# InkTimevf.net
KiCad netlist of a schematic drawn in EAGLE
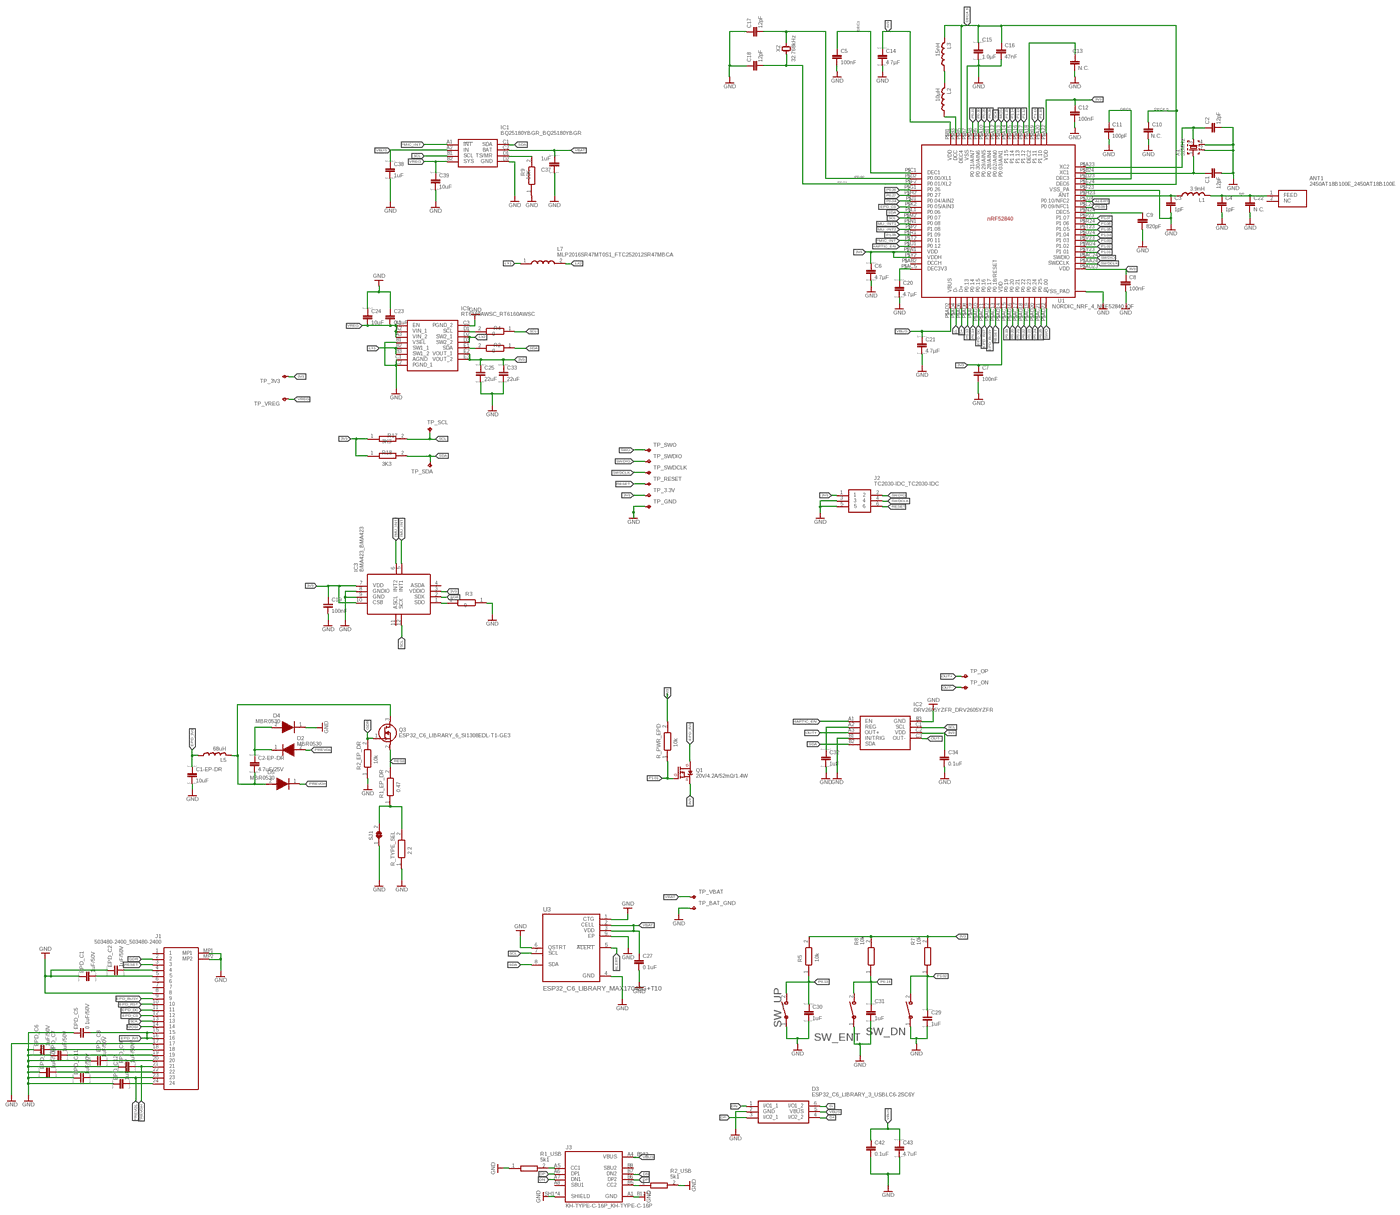
[diagram p0: schematic, sheet 1, overview]
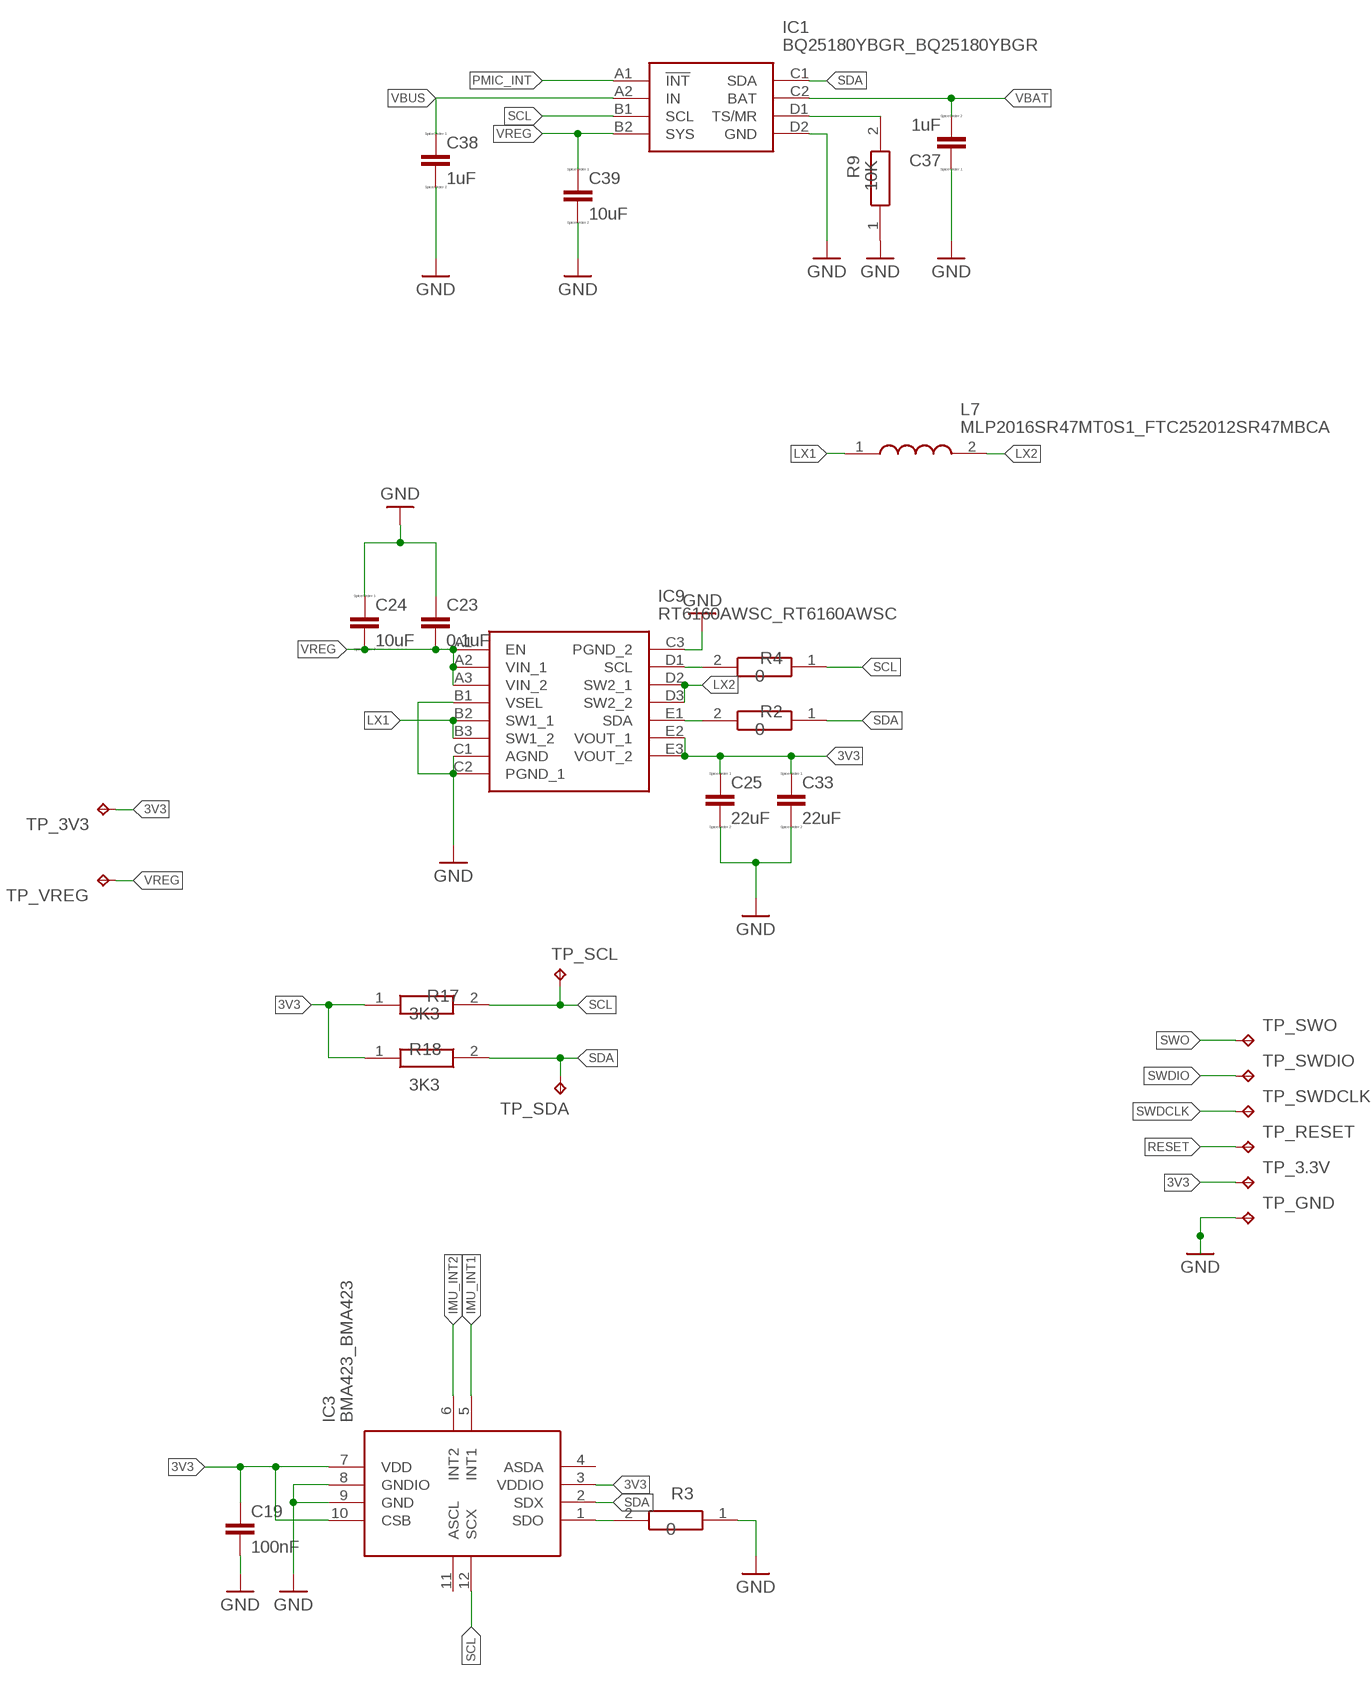
[diagram p1: schematic, sheet 1, part 1 of 4]
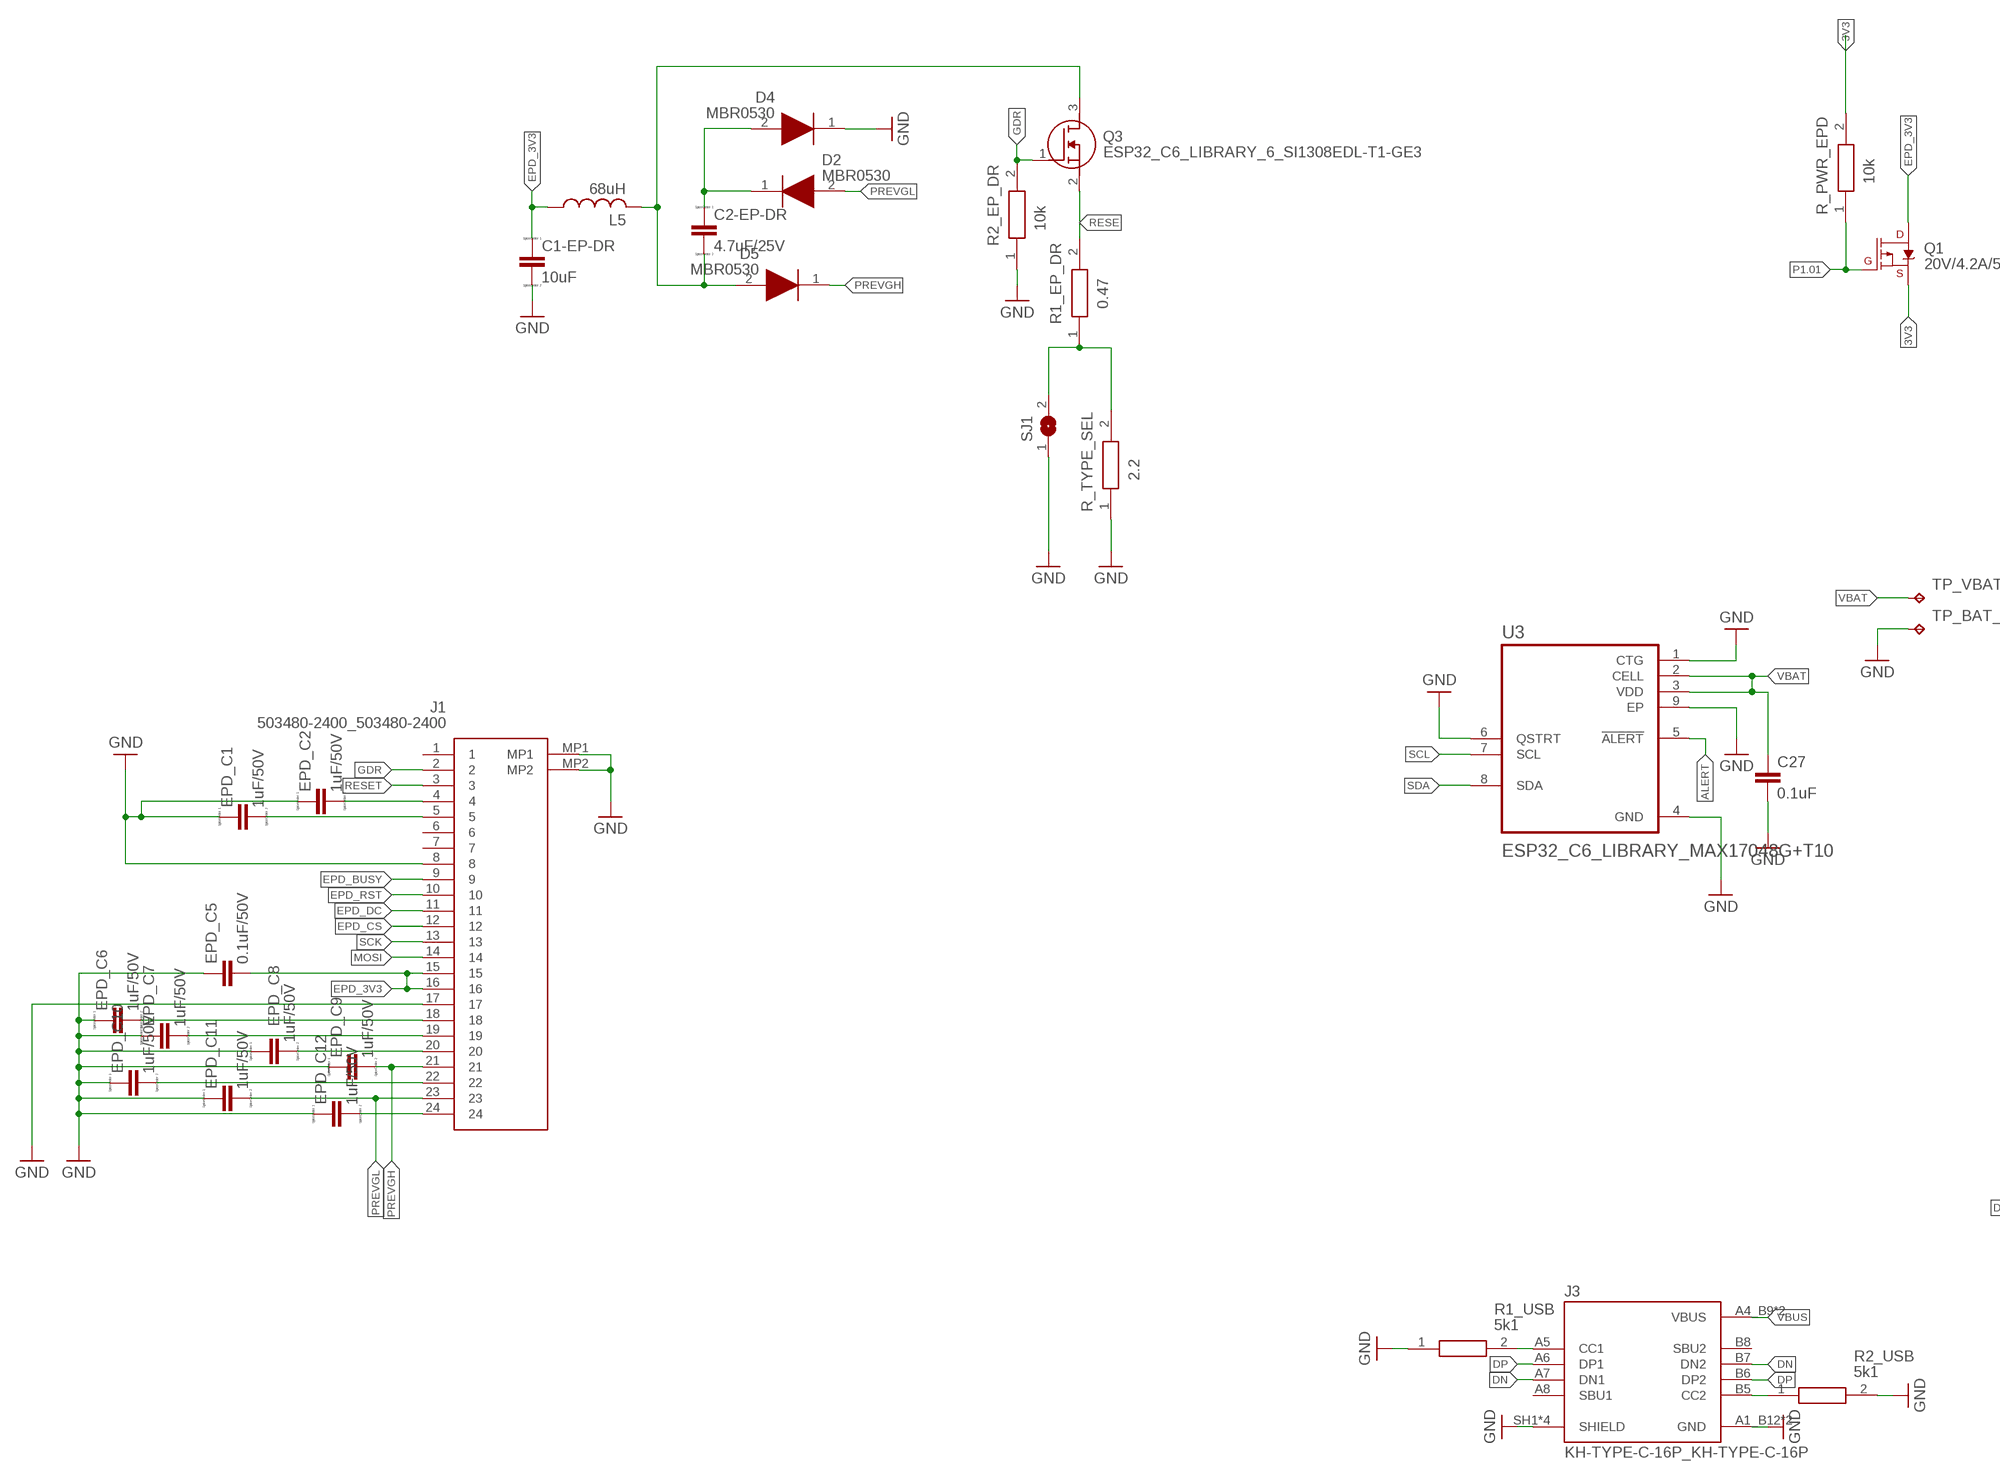
[diagram p2: schematic, sheet 1, part 2 of 4]
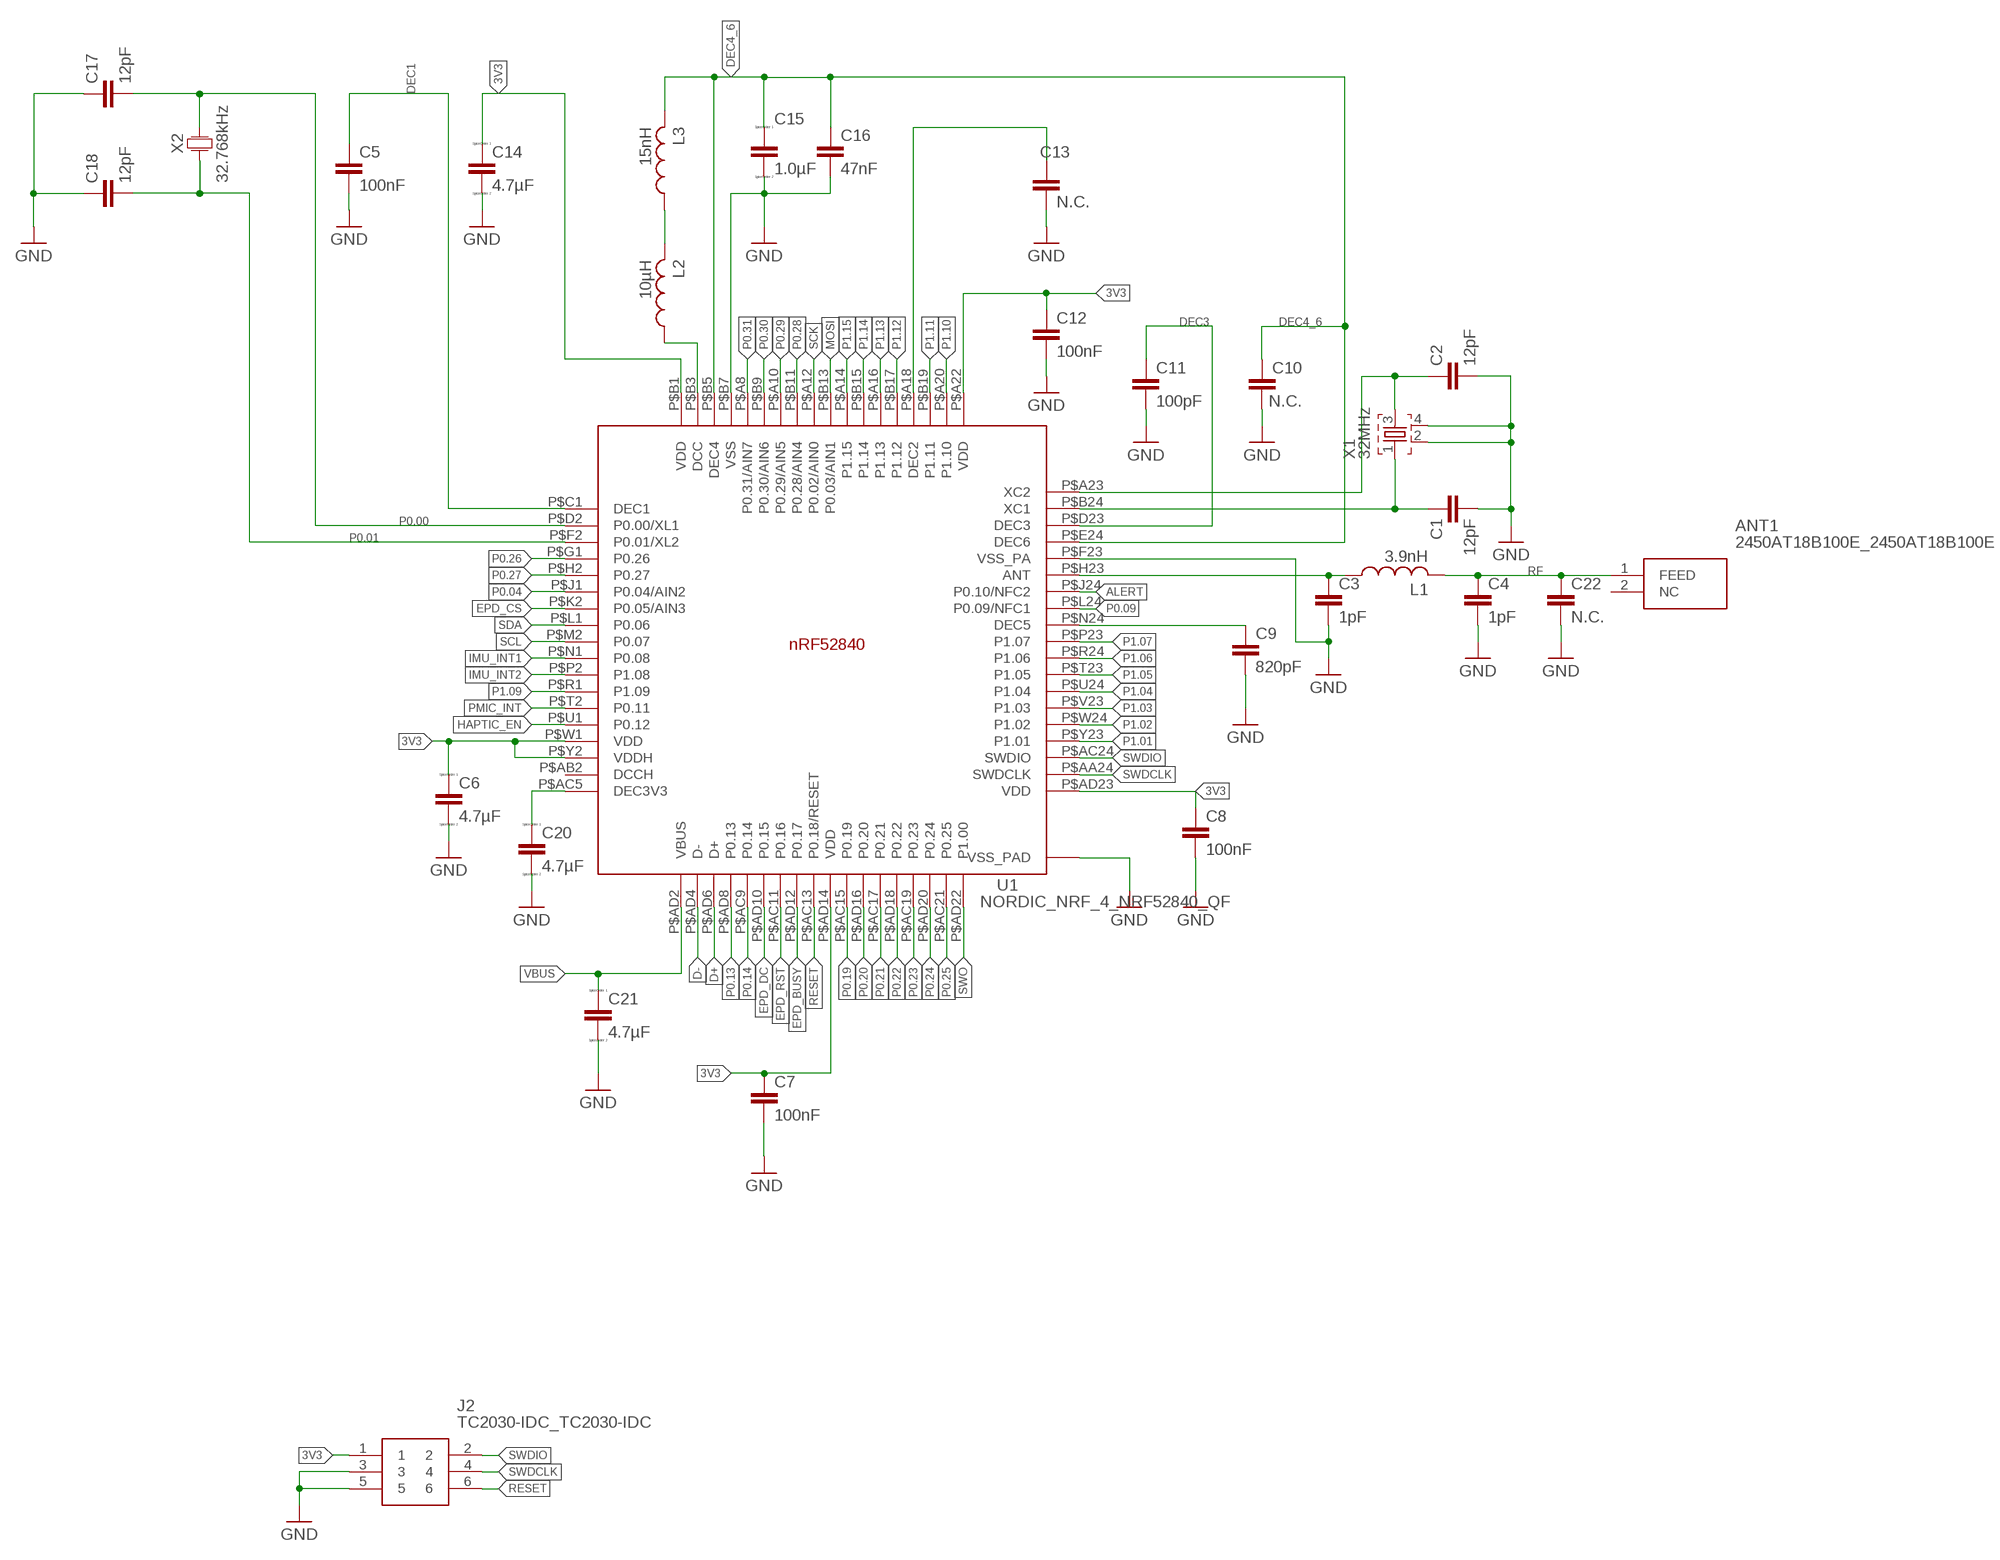
[diagram p3: schematic, sheet 1, part 3 of 4]
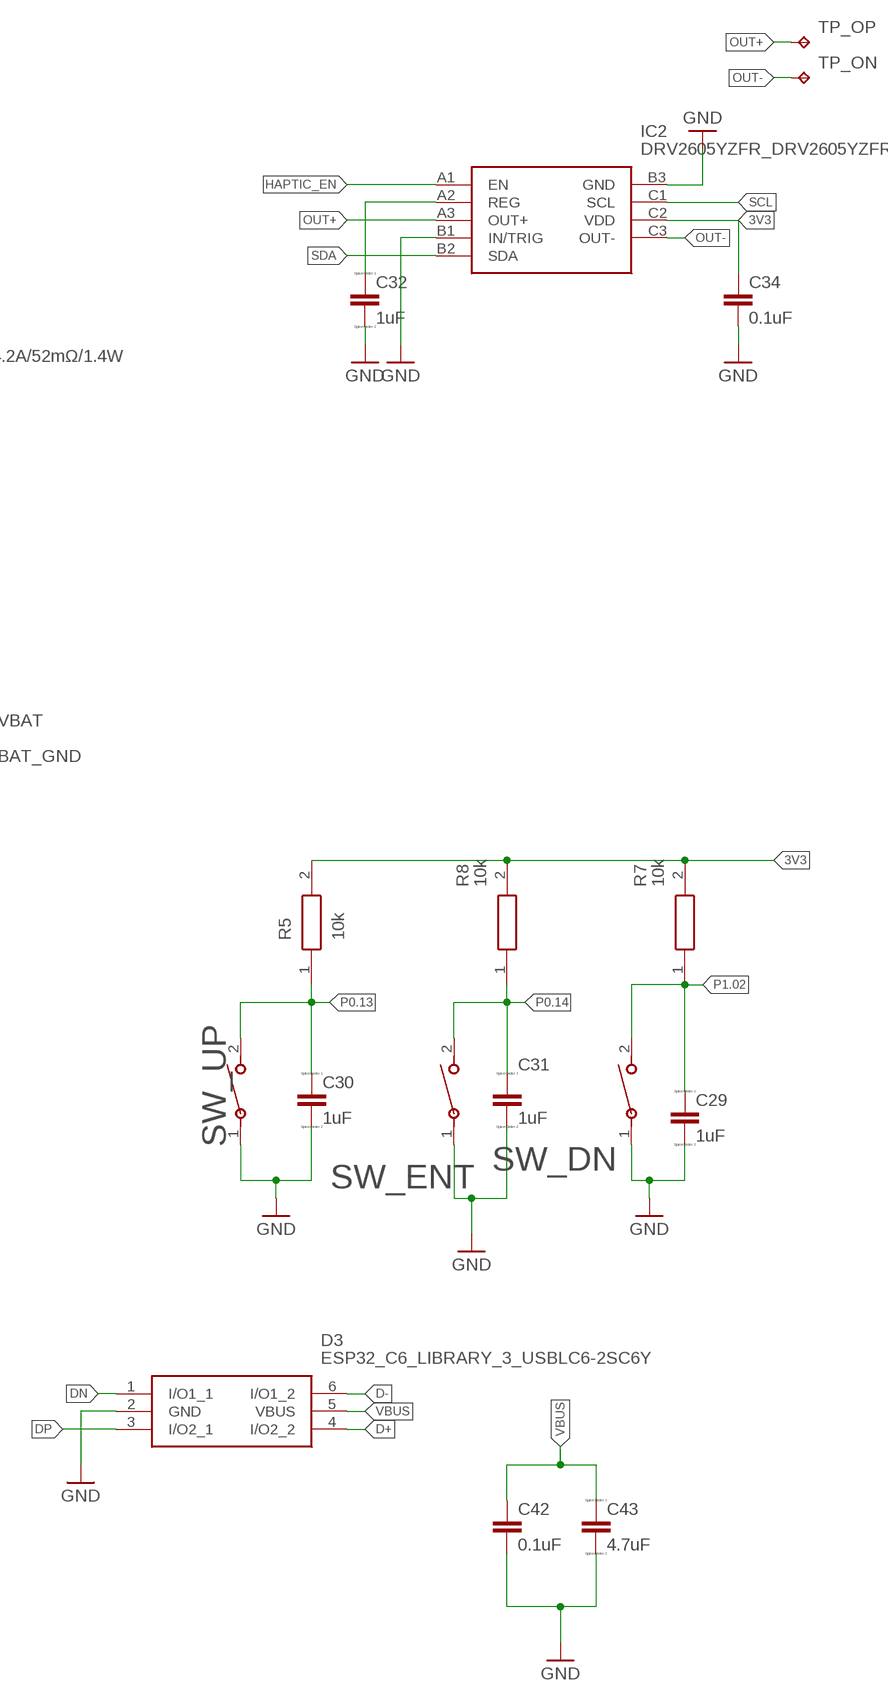
[diagram p4: schematic, sheet 1, part 4 of 4]

(export (version "E")
  (design (tool "Eeschema 10.0.6"))
  (components
    (comp (ref "ANT1")
      (value "2450AT18B100E_2450AT18B100E")
      (footprint "eagle-import:2450AT18B100E_ANTC3216X140N")
      (fields
        (field (name "ARROW_PART_NUMBER") "2450AT18B100E")
        (field (name "MOUSER_PART_NUMBER") "609-2450AT18B100E")
      )
      (libsource (lib "eagle-import") (part "2450AT18B100E_2450AT18B100E"))
    )
    (comp (ref "C1")
      (value "12pF")
      (footprint "eagle-import:NORDIC_NRF_3_RESC0201_L")
      (libsource (lib "eagle-import") (part "NORDIC_NRF_3_CAPACITOR_0201_L"))
    )
    (comp (ref "C1-EP-DR")
      (value "10uF")
      (footprint "eagle-import:ESP32_C6_LIBRARY_1_ESP32_WROVER_EAGLE-LTSPICE_C0402")
      (libsource (lib "eagle-import") (part "ESP32_C6_LIBRARY_1_ESP32_WROVER_EAGLE-LTSPICE_CC0402"))
    )
    (comp (ref "C2")
      (value "12pF")
      (footprint "eagle-import:NORDIC_NRF_3_RESC0201_L")
      (libsource (lib "eagle-import") (part "NORDIC_NRF_3_CAPACITOR_0201_L"))
    )
    (comp (ref "C2-EP-DR")
      (value "4.7uF/25V")
      (footprint "eagle-import:ESP32_C6_LIBRARY_1_ESP32_WROVER_EAGLE-LTSPICE_C0402")
      (libsource (lib "eagle-import") (part "ESP32_C6_LIBRARY_1_ESP32_WROVER_EAGLE-LTSPICE_CC0402"))
    )
    (comp (ref "C3")
      (value "1pF")
      (footprint "eagle-import:NORDIC_NRF_3_RESC0201_L")
      (libsource (lib "eagle-import") (part "NORDIC_NRF_3_CAPACITOR_0201_L"))
    )
    (comp (ref "C4")
      (value "1pF")
      (footprint "eagle-import:NORDIC_NRF_3_RESC0201_L")
      (libsource (lib "eagle-import") (part "NORDIC_NRF_3_CAPACITOR_0201_L"))
    )
    (comp (ref "C5")
      (value "100nF")
      (footprint "eagle-import:NORDIC_NRF_3_RESC0201_L")
      (libsource (lib "eagle-import") (part "NORDIC_NRF_3_CAPACITOR_0201_L"))
    )
    (comp (ref "C6")
      (value "4.7µF")
      (footprint "eagle-import:ESP32_C6_LIBRARY_1_ESP32_WROVER_EAGLE-LTSPICE_C0402")
      (libsource (lib "eagle-import") (part "ESP32_C6_LIBRARY_1_ESP32_WROVER_EAGLE-LTSPICE_CC0402"))
    )
    (comp (ref "C7")
      (value "100nF")
      (footprint "eagle-import:NORDIC_NRF_3_RESC0201_L")
      (libsource (lib "eagle-import") (part "NORDIC_NRF_3_CAPACITOR_0201_L"))
    )
    (comp (ref "C8")
      (value "100nF")
      (footprint "eagle-import:NORDIC_NRF_3_RESC0201_L")
      (libsource (lib "eagle-import") (part "NORDIC_NRF_3_CAPACITOR_0201_L"))
    )
    (comp (ref "C9")
      (value "820pF")
      (footprint "eagle-import:NORDIC_NRF_3_RESC0201_L")
      (libsource (lib "eagle-import") (part "NORDIC_NRF_3_CAPACITOR_0201_L"))
    )
    (comp (ref "C10")
      (value "N.C.")
      (footprint "eagle-import:NORDIC_NRF_3_RESC0201_L")
      (libsource (lib "eagle-import") (part "NORDIC_NRF_3_CAPACITOR_0201_L"))
    )
    (comp (ref "C11")
      (value "100pF")
      (footprint "eagle-import:NORDIC_NRF_3_RESC0201_L")
      (libsource (lib "eagle-import") (part "NORDIC_NRF_3_CAPACITOR_0201_L"))
    )
    (comp (ref "C12")
      (value "100nF")
      (footprint "eagle-import:NORDIC_NRF_3_RESC0201_L")
      (libsource (lib "eagle-import") (part "NORDIC_NRF_3_CAPACITOR_0201_L"))
    )
    (comp (ref "C13")
      (value "N.C.")
      (footprint "eagle-import:NORDIC_NRF_3_RESC0201_L")
      (libsource (lib "eagle-import") (part "NORDIC_NRF_3_CAPACITOR_0201_L"))
    )
    (comp (ref "C14")
      (value "4.7µF")
      (footprint "eagle-import:ESP32_C6_LIBRARY_1_ESP32_WROVER_EAGLE-LTSPICE_C0402")
      (libsource (lib "eagle-import") (part "ESP32_C6_LIBRARY_1_ESP32_WROVER_EAGLE-LTSPICE_CC0402"))
    )
    (comp (ref "C15")
      (value "1.0µF")
      (footprint "eagle-import:ESP32_C6_LIBRARY_1_ESP32_WROVER_EAGLE-LTSPICE_C0402")
      (libsource (lib "eagle-import") (part "ESP32_C6_LIBRARY_1_ESP32_WROVER_EAGLE-LTSPICE_CC0402"))
    )
    (comp (ref "C16")
      (value "47nF")
      (footprint "eagle-import:NORDIC_NRF_3_RESC0201_L")
      (libsource (lib "eagle-import") (part "NORDIC_NRF_3_CAPACITOR_0201_L"))
    )
    (comp (ref "C17")
      (value "12pF")
      (footprint "eagle-import:NORDIC_NRF_3_RESC0201_L")
      (libsource (lib "eagle-import") (part "NORDIC_NRF_3_CAPACITOR_0201_L"))
    )
    (comp (ref "C18")
      (value "12pF")
      (footprint "eagle-import:NORDIC_NRF_3_RESC0201_L")
      (libsource (lib "eagle-import") (part "NORDIC_NRF_3_CAPACITOR_0201_L"))
    )
    (comp (ref "C19")
      (value "100nF")
      (footprint "eagle-import:NORDIC_NRF_3_RESC0201_L")
      (libsource (lib "eagle-import") (part "NORDIC_NRF_3_CAPACITOR_0201_L"))
    )
    (comp (ref "C20")
      (value "4.7µF")
      (footprint "eagle-import:ESP32_C6_LIBRARY_1_ESP32_WROVER_EAGLE-LTSPICE_C0402")
      (libsource (lib "eagle-import") (part "ESP32_C6_LIBRARY_1_ESP32_WROVER_EAGLE-LTSPICE_CC0402"))
    )
    (comp (ref "C21")
      (value "4.7µF")
      (footprint "eagle-import:ESP32_C6_LIBRARY_1_ESP32_WROVER_EAGLE-LTSPICE_C0402")
      (libsource (lib "eagle-import") (part "ESP32_C6_LIBRARY_1_ESP32_WROVER_EAGLE-LTSPICE_CC0402"))
    )
    (comp (ref "C22")
      (value "N.C.")
      (footprint "eagle-import:NORDIC_NRF_3_RESC0201_L")
      (libsource (lib "eagle-import") (part "NORDIC_NRF_3_CAPACITOR_0201_L"))
    )
    (comp (ref "C23")
      (value "0.1uF")
      (footprint "eagle-import:NORDIC_NRF_3_RESC0201_L")
      (libsource (lib "eagle-import") (part "NORDIC_NRF_3_CAPACITOR_0201_L"))
    )
    (comp (ref "C24")
      (value "10uF")
      (footprint "eagle-import:ESP32_C6_LIBRARY_1_ESP32_WROVER_EAGLE-LTSPICE_C0402")
      (libsource (lib "eagle-import") (part "ESP32_C6_LIBRARY_1_ESP32_WROVER_EAGLE-LTSPICE_CC0402"))
    )
    (comp (ref "C25")
      (value "22uF")
      (footprint "eagle-import:ESP32_C6_LIBRARY_1_ESP32_WROVER_EAGLE-LTSPICE_C0402")
      (libsource (lib "eagle-import") (part "ESP32_C6_LIBRARY_1_ESP32_WROVER_EAGLE-LTSPICE_CC0402"))
    )
    (comp (ref "C27")
      (value "0.1uF")
      (footprint "eagle-import:NORDIC_NRF_3_RESC0201_L")
      (libsource (lib "eagle-import") (part "NORDIC_NRF_3_CAPACITOR_0201_L"))
    )
    (comp (ref "C29")
      (value "1uF")
      (footprint "eagle-import:ESP32_C6_LIBRARY_1_ESP32_WROVER_EAGLE-LTSPICE_C0402")
      (libsource (lib "eagle-import") (part "ESP32_C6_LIBRARY_1_ESP32_WROVER_EAGLE-LTSPICE_CC0402"))
    )
    (comp (ref "C30")
      (value "1uF")
      (footprint "eagle-import:ESP32_C6_LIBRARY_1_ESP32_WROVER_EAGLE-LTSPICE_C0402")
      (libsource (lib "eagle-import") (part "ESP32_C6_LIBRARY_1_ESP32_WROVER_EAGLE-LTSPICE_CC0402"))
    )
    (comp (ref "C31")
      (value "1uF")
      (footprint "eagle-import:ESP32_C6_LIBRARY_1_ESP32_WROVER_EAGLE-LTSPICE_C0402")
      (libsource (lib "eagle-import") (part "ESP32_C6_LIBRARY_1_ESP32_WROVER_EAGLE-LTSPICE_CC0402"))
    )
    (comp (ref "C32")
      (value "1uF")
      (footprint "eagle-import:ESP32_C6_LIBRARY_1_ESP32_WROVER_EAGLE-LTSPICE_C0402")
      (libsource (lib "eagle-import") (part "ESP32_C6_LIBRARY_1_ESP32_WROVER_EAGLE-LTSPICE_CC0402"))
    )
    (comp (ref "C33")
      (value "22uF")
      (footprint "eagle-import:ESP32_C6_LIBRARY_1_ESP32_WROVER_EAGLE-LTSPICE_C0402")
      (libsource (lib "eagle-import") (part "ESP32_C6_LIBRARY_1_ESP32_WROVER_EAGLE-LTSPICE_CC0402"))
    )
    (comp (ref "C34")
      (value "0.1uF")
      (footprint "eagle-import:NORDIC_NRF_3_RESC0201_L")
      (libsource (lib "eagle-import") (part "NORDIC_NRF_3_CAPACITOR_0201_L"))
    )
    (comp (ref "C37")
      (value "1uF")
      (footprint "eagle-import:ESP32_C6_LIBRARY_1_ESP32_WROVER_EAGLE-LTSPICE_C0402")
      (libsource (lib "eagle-import") (part "ESP32_C6_LIBRARY_1_ESP32_WROVER_EAGLE-LTSPICE_CC0402"))
    )
    (comp (ref "C38")
      (value "1uF")
      (footprint "eagle-import:ESP32_C6_LIBRARY_1_ESP32_WROVER_EAGLE-LTSPICE_C0402")
      (libsource (lib "eagle-import") (part "ESP32_C6_LIBRARY_1_ESP32_WROVER_EAGLE-LTSPICE_CC0402"))
    )
    (comp (ref "C39")
      (value "10uF")
      (footprint "eagle-import:ESP32_C6_LIBRARY_1_ESP32_WROVER_EAGLE-LTSPICE_C0402")
      (libsource (lib "eagle-import") (part "ESP32_C6_LIBRARY_1_ESP32_WROVER_EAGLE-LTSPICE_CC0402"))
    )
    (comp (ref "C42")
      (value "0.1uF")
      (footprint "eagle-import:NORDIC_NRF_3_RESC0201_L")
      (libsource (lib "eagle-import") (part "NORDIC_NRF_3_CAPACITOR_0201_L"))
    )
    (comp (ref "C43")
      (value "4.7uF")
      (footprint "eagle-import:ESP32_C6_LIBRARY_1_ESP32_WROVER_EAGLE-LTSPICE_C0402")
      (libsource (lib "eagle-import") (part "ESP32_C6_LIBRARY_1_ESP32_WROVER_EAGLE-LTSPICE_CC0402"))
    )
    (comp (ref "D2")
      (value "MBR0530")
      (footprint "eagle-import:ESP32_C6_LIBRARY_5_SOD3716X135N")
      (fields (field (name "MF") "ON Semiconductor"))
      (libsource (lib "eagle-import") (part "ESP32_C6_LIBRARY_5_MBR0530"))
    )
    (comp (ref "D3")
      (value "ESP32_C6_LIBRARY_3_USBLC6-2SC6Y")
      (footprint "eagle-import:ESP32_C6_LIBRARY_3_SOT95P280X145-6N")
      (fields (field (name "MF") "STMicroelectronics") (field (name "MP") "USBLC6-2SC6Y"))
      (libsource (lib "eagle-import") (part "ESP32_C6_LIBRARY_3_USBLC6-2SC6Y"))
    )
    (comp (ref "D4")
      (value "MBR0530")
      (footprint "eagle-import:ESP32_C6_LIBRARY_5_SOD3716X135N")
      (fields (field (name "MF") "ON Semiconductor"))
      (libsource (lib "eagle-import") (part "ESP32_C6_LIBRARY_5_MBR0530"))
    )
    (comp (ref "D5")
      (value "MBR0530")
      (footprint "eagle-import:ESP32_C6_LIBRARY_5_SOD3716X135N")
      (fields (field (name "MF") "ON Semiconductor"))
      (libsource (lib "eagle-import") (part "ESP32_C6_LIBRARY_5_MBR0530"))
    )
    (comp (ref "EPD_C1")
      (value "1uF/50V")
      (footprint "eagle-import:ESP32_C6_LIBRARY_1_ESP32_WROVER_EAGLE-LTSPICE_C0402")
      (libsource (lib "eagle-import") (part "ESP32_C6_LIBRARY_1_ESP32_WROVER_EAGLE-LTSPICE_CC0402"))
    )
    (comp (ref "EPD_C2")
      (value "1uF/50V")
      (footprint "eagle-import:ESP32_C6_LIBRARY_1_ESP32_WROVER_EAGLE-LTSPICE_C0402")
      (libsource (lib "eagle-import") (part "ESP32_C6_LIBRARY_1_ESP32_WROVER_EAGLE-LTSPICE_CC0402"))
    )
    (comp (ref "EPD_C5")
      (value "0.1uF/50V")
      (footprint "eagle-import:NORDIC_NRF_3_RESC0201_L")
      (libsource (lib "eagle-import") (part "NORDIC_NRF_3_CAPACITOR_0201_L"))
    )
    (comp (ref "EPD_C6")
      (value "1uF/50V")
      (footprint "eagle-import:ESP32_C6_LIBRARY_1_ESP32_WROVER_EAGLE-LTSPICE_C0402")
      (libsource (lib "eagle-import") (part "ESP32_C6_LIBRARY_1_ESP32_WROVER_EAGLE-LTSPICE_CC0402"))
    )
    (comp (ref "EPD_C7")
      (value "1uF/50V")
      (footprint "eagle-import:ESP32_C6_LIBRARY_1_ESP32_WROVER_EAGLE-LTSPICE_C0402")
      (libsource (lib "eagle-import") (part "ESP32_C6_LIBRARY_1_ESP32_WROVER_EAGLE-LTSPICE_CC0402"))
    )
    (comp (ref "EPD_C8")
      (value "1uF/50V")
      (footprint "eagle-import:ESP32_C6_LIBRARY_1_ESP32_WROVER_EAGLE-LTSPICE_C0402")
      (libsource (lib "eagle-import") (part "ESP32_C6_LIBRARY_1_ESP32_WROVER_EAGLE-LTSPICE_CC0402"))
    )
    (comp (ref "EPD_C9")
      (value "1uF/50V")
      (footprint "eagle-import:ESP32_C6_LIBRARY_1_ESP32_WROVER_EAGLE-LTSPICE_C0402")
      (libsource (lib "eagle-import") (part "ESP32_C6_LIBRARY_1_ESP32_WROVER_EAGLE-LTSPICE_CC0402"))
    )
    (comp (ref "EPD_C10")
      (value "1uF/50V")
      (footprint "eagle-import:ESP32_C6_LIBRARY_1_ESP32_WROVER_EAGLE-LTSPICE_C0402")
      (libsource (lib "eagle-import") (part "ESP32_C6_LIBRARY_1_ESP32_WROVER_EAGLE-LTSPICE_CC0402"))
    )
    (comp (ref "EPD_C11")
      (value "1uF/50V")
      (footprint "eagle-import:ESP32_C6_LIBRARY_1_ESP32_WROVER_EAGLE-LTSPICE_C0402")
      (libsource (lib "eagle-import") (part "ESP32_C6_LIBRARY_1_ESP32_WROVER_EAGLE-LTSPICE_CC0402"))
    )
    (comp (ref "EPD_C12")
      (value "1uF/50V")
      (footprint "eagle-import:ESP32_C6_LIBRARY_1_ESP32_WROVER_EAGLE-LTSPICE_C0402")
      (libsource (lib "eagle-import") (part "ESP32_C6_LIBRARY_1_ESP32_WROVER_EAGLE-LTSPICE_CC0402"))
    )
    (comp (ref "IC1")
      (value "BQ25180YBGR_BQ25180YBGR")
      (footprint "eagle-import:BQ25180YBGR_BGA8C40P2X4_100X155X50")
      (fields
        (field (name "ARROW_PART_NUMBER") "BQ25180YBGR")
        (field (name "MOUSER_PART_NUMBER") "595-BQ25180YBGR")
      )
      (libsource (lib "eagle-import") (part "BQ25180YBGR_BQ25180YBGR"))
    )
    (comp (ref "IC2")
      (value "DRV2605YZFR_DRV2605YZFR")
      (footprint "eagle-import:DRV2605YZFR_BGA9C50P3X3_144X144X62")
      (fields (field (name "ARROW_PART_NUMBER") "DRV2605YZFR"))
      (libsource (lib "eagle-import") (part "DRV2605YZFR_DRV2605YZFR"))
    )
    (comp (ref "IC3")
      (value "BMA423_BMA423")
      (footprint "eagle-import:BMA423_BMA423")
      (fields (field (name "ARROW_PART_NUMBER") "BMA423") (field (name "MOUSER_PART_NUMBER") "262-BMA423"))
      (libsource (lib "eagle-import") (part "BMA423_BMA423"))
    )
    (comp (ref "IC9")
      (value "RT6160AWSC_RT6160AWSC")
      (footprint "eagle-import:RT6160AWSC_BGA15C40P3X5_140X230X60")
      (fields
        (field (name "MANUFACTURER_PART_NUMBER") "RT6160AWSC")
        (field (name "MOUSER_PART_NUMBER") "835-RT6160AWSC")
      )
      (libsource (lib "eagle-import") (part "RT6160AWSC_RT6160AWSC"))
    )
    (comp (ref "J1")
      (value "503480-2400_503480-2400")
      (footprint "eagle-import:503480-2400_5034802400")
      (fields
        (field (name "MANUFACTURER_PART_NUMBER") "503480-2400")
        (field (name "MOUSER_PART_NUMBER") "538-503480-2400")
      )
      (libsource (lib "eagle-import") (part "503480-2400_503480-2400"))
    )
    (comp (ref "J2")
      (value "TC2030-IDC_TC2030-IDC")
      (footprint "eagle-import:TC2030-IDC_TC2030IDC")
      (fields (field (name "MANUFACTURER_PART_NUMBER") "TC2030-IDC"))
      (libsource (lib "eagle-import") (part "TC2030-IDC_TC2030-IDC"))
    )
    (comp (ref "J3")
      (value "KH-TYPE-C-16P_KH-TYPE-C-16P")
      (footprint "eagle-import:KH-TYPE-C-16P_KINGHELM_KH-TYPE-C-16P")
      (fields (field (name "MF") "kinghelm") (field (name "MP") "KH-TYPE-C-16P"))
      (libsource (lib "eagle-import") (part "KH-TYPE-C-16P_KH-TYPE-C-16P"))
    )
    (comp (ref "L1")
      (value "3.9nH")
      (footprint "eagle-import:NORDIC_NRF_2_RESC0402_L")
      (libsource (lib "eagle-import") (part "NORDIC_NRF_2_INDUCTOR_0402_L"))
    )
    (comp (ref "L2")
      (value "10µH")
      (footprint "eagle-import:NORDIC_NRF_2_RESC0402_L")
      (libsource (lib "eagle-import") (part "NORDIC_NRF_2_INDUCTOR_0402_L"))
    )
    (comp (ref "L3")
      (value "15nH")
      (footprint "eagle-import:NORDIC_NRF_2_RESC0402_L")
      (libsource (lib "eagle-import") (part "NORDIC_NRF_2_INDUCTOR_0402_L"))
    )
    (comp (ref "L5")
      (value "68uH")
      (footprint "eagle-import:NORDIC_NRF_2_RESC0402_L")
      (libsource (lib "eagle-import") (part "NORDIC_NRF_2_INDUCTOR_0402_L"))
    )
    (comp (ref "L7")
      (value "MLP2016SR47MT0S1_FTC252012SR47MBCA")
      (footprint "eagle-import:MLP2016SR47MT0S1_INDC2016X100N")
      (fields (field (name "MANUFACTURER_PART_NUMBER") "FTC252012SR47MBCA"))
      (libsource (lib "eagle-import") (part "MLP2016SR47MT0S1_FTC252012SR47MBCA"))
    )
    (comp (ref "Q1")
      (value "20V/4.2A/52mΩ/1.4W")
      (footprint "eagle-import:ESP32_C6_LIBRARY_4_ESP32_C6_LIBRARY_4_ESP32_C6_LIBRARY_4_ESP32_C6_LIBRARY_4_ESP32_WROVER_SPARKFUN-DISCRETESEMI_SOT23-3")
      (libsource (lib "eagle-import") (part "ESP32_C6_LIBRARY_4_ESP32_WROVER_SPARKFUN-DISCRETESEMI_MOSFET_PCH-DMG2305UX-7"))
    )
    (comp (ref "Q3")
      (value "ESP32_C6_LIBRARY_6_SI1308EDL-T1-GE3")
      (footprint "eagle-import:ESP32_C6_LIBRARY_6_SOT65P210X110-3N")
      (fields (field (name "MF") "Vishay Siliconix") (field (name "MP") "SI1308EDL-T1-GE3"))
      (libsource (lib "eagle-import") (part "ESP32_C6_LIBRARY_6_SI1308EDL-T1-GE3"))
    )
    (comp (ref "R1_EP_DR")
      (value "0.47")
      (footprint "eagle-import:CPF0201D7K68C1_0201")
      (libsource (lib "eagle-import") (part "CPF0201D7K68C1_CPF0201D7K68C1"))
    )
    (comp (ref "R1_USB")
      (value "5k1")
      (footprint "eagle-import:CPF0201D7K68C1_0201")
      (libsource (lib "eagle-import") (part "CPF0201D7K68C1_CPF0201D7K68C1"))
    )
    (comp (ref "R2")
      (value "0")
      (footprint "eagle-import:ERA-1AEB3401C_0201")
      (libsource (lib "eagle-import") (part "ERA-1AEB3401C_CPF0201D7K68C1"))
    )
    (comp (ref "R2_EP_DR")
      (value "10k")
      (footprint "eagle-import:CPF0201D7K68C1_0201")
      (libsource (lib "eagle-import") (part "CPF0201D7K68C1_CPF0201D7K68C1"))
    )
    (comp (ref "R2_USB")
      (value "5k1")
      (footprint "eagle-import:CPF0201D7K68C1_0201")
      (libsource (lib "eagle-import") (part "CPF0201D7K68C1_CPF0201D7K68C1"))
    )
    (comp (ref "R3")
      (value "0")
      (footprint "eagle-import:CPF0201D7K68C1_0201")
      (libsource (lib "eagle-import") (part "CPF0201D7K68C1_CPF0201D7K68C1"))
    )
    (comp (ref "R4")
      (value "0")
      (footprint "eagle-import:ERA-1AEB3401C_0201")
      (libsource (lib "eagle-import") (part "ERA-1AEB3401C_CPF0201D7K68C1"))
    )
    (comp (ref "R5")
      (value "10k")
      (footprint "eagle-import:CPF0201D7K68C1_0201")
      (libsource (lib "eagle-import") (part "CPF0201D7K68C1_CPF0201D7K68C1"))
    )
    (comp (ref "R7")
      (value "10k")
      (footprint "eagle-import:CPF0201D7K68C1_0201")
      (libsource (lib "eagle-import") (part "CPF0201D7K68C1_CPF0201D7K68C1"))
    )
    (comp (ref "R8")
      (value "10k")
      (footprint "eagle-import:CPF0201D7K68C1_0201")
      (libsource (lib "eagle-import") (part "CPF0201D7K68C1_CPF0201D7K68C1"))
    )
    (comp (ref "R9")
      (value "10K")
      (footprint "eagle-import:CPF0201D7K68C1_0201")
      (libsource (lib "eagle-import") (part "CPF0201D7K68C1_CPF0201D7K68C1"))
    )
    (comp (ref "R17")
      (value "3K3")
      (footprint "eagle-import:ERA-1AEB3401C_0201")
      (libsource (lib "eagle-import") (part "ERA-1AEB3401C_CPF0201D7K68C1"))
    )
    (comp (ref "R18")
      (value "3K3")
      (footprint "eagle-import:ERA-1AEB3401C_0201")
      (libsource (lib "eagle-import") (part "ERA-1AEB3401C_CPF0201D7K68C1"))
    )
    (comp (ref "R_PWR_EPD")
      (value "10k")
      (footprint "eagle-import:ERA-1AEB3401C_0201")
      (libsource (lib "eagle-import") (part "ERA-1AEB3401C_CPF0201D7K68C1"))
    )
    (comp (ref "R_TYPE_SEL")
      (value "2.2")
      (footprint "eagle-import:CPF0201D7K68C1_0201")
      (libsource (lib "eagle-import") (part "CPF0201D7K68C1_CPF0201D7K68C1"))
    )
    (comp (ref "SJ1")
      (value "ESP32_C6_LIBRARY_7_JUMPER_SJ")
      (footprint "eagle-import:ESP32_C6_LIBRARY_7_JUMPER_SJ")
      (libsource (lib "eagle-import") (part "ESP32_C6_LIBRARY_7_JUMPER_SJ"))
    )
    (comp (ref "SW_DN")
      (value "2025-10-22_07-23-44_LIBRARY_EVP-AKE31ASW_EVP-AKE31A_PAN")
      (footprint "eagle-import:2025-10-22_07-23-44_LIBRARY_SW_EVP-AKE31A_PAN")
      (fields
        (field (name "MANUFACTURER_PART_NUMBER") "EVP-AKE31A")
        (field (name "COPYRIGHT") "Copyright (C) 2025 Ultra Librarian. All rights reserved.")
      )
      (libsource (lib "eagle-import") (part "2025-10-22_07-23-44_LIBRARY_EVP-AKE31ASW_EVP-AKE31A_PAN"))
    )
    (comp (ref "SW_ENT")
      (value "2025-10-22_07-23-44_LIBRARY_EVP-AKE31ASW_EVP-AKE31A_PAN")
      (footprint "eagle-import:2025-10-22_07-23-44_LIBRARY_SW_EVP-AKE31A_PAN")
      (fields
        (field (name "MANUFACTURER_PART_NUMBER") "EVP-AKE31A")
        (field (name "COPYRIGHT") "Copyright (C) 2025 Ultra Librarian. All rights reserved.")
      )
      (libsource (lib "eagle-import") (part "2025-10-22_07-23-44_LIBRARY_EVP-AKE31ASW_EVP-AKE31A_PAN"))
    )
    (comp (ref "SW_UP")
      (value "2025-10-22_07-23-44_LIBRARY_EVP-AKE31ASW_EVP-AKE31A_PAN")
      (footprint "eagle-import:2025-10-22_07-23-44_LIBRARY_SW_EVP-AKE31A_PAN")
      (fields
        (field (name "MANUFACTURER_PART_NUMBER") "EVP-AKE31A")
        (field (name "COPYRIGHT") "Copyright (C) 2025 Ultra Librarian. All rights reserved.")
      )
      (libsource (lib "eagle-import") (part "2025-10-22_07-23-44_LIBRARY_EVP-AKE31ASW_EVP-AKE31A_PAN"))
    )
    (comp (ref "TP_3.3V")
      (value "HECTOR_WATCH_1_TPTP20R")
      (footprint "eagle-import:HECTOR_WATCH_1_TP20R")
      (libsource (lib "eagle-import") (part "HECTOR_WATCH_1_TPTP20R"))
    )
    (comp (ref "TP_3V3")
      (value "HECTOR_WATCH_1_TPTP20R")
      (footprint "eagle-import:HECTOR_WATCH_1_TP20R")
      (libsource (lib "eagle-import") (part "HECTOR_WATCH_1_TPTP20R"))
    )
    (comp (ref "TP_BAT_GND")
      (value "HECTOR_WATCH_1_TPTP20R")
      (footprint "eagle-import:HECTOR_WATCH_1_TP20R")
      (libsource (lib "eagle-import") (part "HECTOR_WATCH_1_TPTP20R"))
    )
    (comp (ref "TP_GND")
      (value "HECTOR_WATCH_1_TPTP20R")
      (footprint "eagle-import:HECTOR_WATCH_1_TP20R")
      (libsource (lib "eagle-import") (part "HECTOR_WATCH_1_TPTP20R"))
    )
    (comp (ref "TP_ON")
      (value "HECTOR_WATCH_1_TPTP20R")
      (footprint "eagle-import:HECTOR_WATCH_1_TP20R")
      (libsource (lib "eagle-import") (part "HECTOR_WATCH_1_TPTP20R"))
    )
    (comp (ref "TP_OP")
      (value "HECTOR_WATCH_1_TPTP20R")
      (footprint "eagle-import:HECTOR_WATCH_1_TP20R")
      (libsource (lib "eagle-import") (part "HECTOR_WATCH_1_TPTP20R"))
    )
    (comp (ref "TP_RESET")
      (value "HECTOR_WATCH_1_TPTP20R")
      (footprint "eagle-import:HECTOR_WATCH_1_TP20R")
      (libsource (lib "eagle-import") (part "HECTOR_WATCH_1_TPTP20R"))
    )
    (comp (ref "TP_SCL")
      (value "HECTOR_WATCH_1_TPTP20R")
      (footprint "eagle-import:HECTOR_WATCH_1_TP20R")
      (libsource (lib "eagle-import") (part "HECTOR_WATCH_1_TPTP20R"))
    )
    (comp (ref "TP_SDA")
      (value "HECTOR_WATCH_1_TPTP20R")
      (footprint "eagle-import:HECTOR_WATCH_1_TP20R")
      (libsource (lib "eagle-import") (part "HECTOR_WATCH_1_TPTP20R"))
    )
    (comp (ref "TP_SWDCLK")
      (value "HECTOR_WATCH_1_TPTP20R")
      (footprint "eagle-import:HECTOR_WATCH_1_TP20R")
      (libsource (lib "eagle-import") (part "HECTOR_WATCH_1_TPTP20R"))
    )
    (comp (ref "TP_SWDIO")
      (value "HECTOR_WATCH_1_TPTP20R")
      (footprint "eagle-import:HECTOR_WATCH_1_TP20R")
      (libsource (lib "eagle-import") (part "HECTOR_WATCH_1_TPTP20R"))
    )
    (comp (ref "TP_SWO")
      (value "HECTOR_WATCH_1_TPTP20R")
      (footprint "eagle-import:HECTOR_WATCH_1_TP20R")
      (libsource (lib "eagle-import") (part "HECTOR_WATCH_1_TPTP20R"))
    )
    (comp (ref "TP_VBAT")
      (value "HECTOR_WATCH_1_TPTP20R")
      (footprint "eagle-import:HECTOR_WATCH_1_TP20R")
      (libsource (lib "eagle-import") (part "HECTOR_WATCH_1_TPTP20R"))
    )
    (comp (ref "TP_VREG")
      (value "HECTOR_WATCH_1_TPTP20R")
      (footprint "eagle-import:HECTOR_WATCH_1_TP20R")
      (libsource (lib "eagle-import") (part "HECTOR_WATCH_1_TPTP20R"))
    )
    (comp (ref "U1")
      (value "NORDIC_NRF_4_NRF52840_QF")
      (footprint "eagle-import:NORDIC_NRF_4_AQFN50P700X700X85_HS-74N")
      (libsource (lib "eagle-import") (part "NORDIC_NRF_4_NRF52840_QF"))
    )
    (comp (ref "U3")
      (value "ESP32_C6_LIBRARY_MAX17048G+T10")
      (footprint "eagle-import:ESP32_C6_LIBRARY_SON50P200X200X80-9N")
      (fields (field (name "MF") "Analog Devices") (field (name "MP") "MAX17048G+T10"))
      (libsource (lib "eagle-import") (part "ESP32_C6_LIBRARY_MAX17048G+T10"))
    )
    (comp (ref "X1")
      (value "32MHz")
      (footprint "eagle-import:NORDIC_NRF_BT-XTAL_2016_N")
      (libsource (lib "eagle-import") (part "NORDIC_NRF_XTAL_32MHZ"))
    )
    (comp (ref "X2")
      (value "32.768kHz")
      (footprint "eagle-import:XTAL330X1051X90N")
      (fields
        (field (name "MANUFACTURER") "TXC CORPORATION")
        (field (name "MPN") "9HT10-32.768KDZF-T")
        (field (name "TOLERANCE") "±20 ppm")
      )
      (libsource (lib "eagle-import") (part "9HT10"))
    )
  )
  (nets
    (net (code "1") (name "/DEC1") (class "Default")
      (node (ref "C5") (pin "1") (pinfunction "1_1") (pintype "passive"))
      (node (ref "U1") (pin "P$C1") (pinfunction "DEC1_P$C1") (pintype "power_in"))
    )
    (net (code "2") (name "/DEC3") (class "Default")
      (node (ref "C11") (pin "1") (pinfunction "1_1") (pintype "passive"))
      (node (ref "U1") (pin "P$D23") (pinfunction "DEC3_P$D23") (pintype "bidirectional"))
    )
    (net (code "3") (name "/P0.00") (class "Default")
      (node (ref "C17") (pin "2") (pinfunction "2_2") (pintype "passive"))
      (node (ref "U1") (pin "P$D2") (pinfunction "P0.00/XL1_P$D2") (pintype "bidirectional"))
      (node (ref "X2") (pin "2") (pinfunction "2_2") (pintype "passive"))
    )
    (net (code "4") (name "/P0.01") (class "Default")
      (node (ref "C18") (pin "2") (pinfunction "2_2") (pintype "passive"))
      (node (ref "U1") (pin "P$F2") (pinfunction "P0.01/XL2_P$F2") (pintype "bidirectional"))
      (node (ref "X2") (pin "1") (pinfunction "1_1") (pintype "passive"))
    )
    (net (code "5") (name "/RF") (class "Default")
      (node (ref "ANT1") (pin "1") (pinfunction "FEED_1") (pintype "input"))
      (node (ref "C22") (pin "1") (pinfunction "1_1") (pintype "passive"))
      (node (ref "C4") (pin "1") (pinfunction "1_1") (pintype "passive"))
      (node (ref "L1") (pin "2") (pinfunction "2_2") (pintype "passive"))
    )
    (net (code "6") (name "3V3") (class "Default")
      (node (ref "C12") (pin "1") (pinfunction "1_1") (pintype "passive"))
      (node (ref "C14") (pin "1") (pinfunction "1_1") (pintype "passive"))
      (node (ref "C19") (pin "1") (pinfunction "1_1") (pintype "passive"))
      (node (ref "C25") (pin "1") (pinfunction "1_1") (pintype "passive"))
      (node (ref "C33") (pin "1") (pinfunction "1_1") (pintype "passive"))
      (node (ref "C34") (pin "1") (pinfunction "1_1") (pintype "passive"))
      (node (ref "C6") (pin "1") (pinfunction "1_1") (pintype "passive"))
      (node (ref "C7") (pin "1") (pinfunction "1_1") (pintype "passive"))
      (node (ref "C8") (pin "1") (pinfunction "1_1") (pintype "passive"))
      (node (ref "IC2") (pin "C2") (pinfunction "VDD_C2") (pintype "bidirectional"))
      (node (ref "IC3") (pin "10") (pinfunction "CSB_10") (pintype "bidirectional"))
      (node (ref "IC3") (pin "3") (pinfunction "VDDIO_3") (pintype "bidirectional"))
      (node (ref "IC3") (pin "7") (pinfunction "VDD_7") (pintype "bidirectional"))
      (node (ref "IC9") (pin "E2") (pinfunction "VOUT_1_E2") (pintype "bidirectional"))
      (node (ref "IC9") (pin "E3") (pinfunction "VOUT_2_E3") (pintype "bidirectional"))
      (node (ref "J2") (pin "1") (pinfunction "1_1") (pintype "bidirectional"))
      (node (ref "Q1") (pin "2") (pinfunction "S_2") (pintype "bidirectional"))
      (node (ref "R17") (pin "1") (pinfunction "1_1") (pintype "bidirectional"))
      (node (ref "R18") (pin "1") (pinfunction "1_1") (pintype "bidirectional"))
      (node (ref "R5") (pin "2") (pinfunction "2_2") (pintype "bidirectional"))
      (node (ref "R7") (pin "2") (pinfunction "2_2") (pintype "bidirectional"))
      (node (ref "R8") (pin "2") (pinfunction "2_2") (pintype "bidirectional"))
      (node (ref "R_PWR_EPD") (pin "2") (pinfunction "2_2") (pintype "bidirectional"))
      (node (ref "TP_3.3V") (pin "TP") (pinfunction "TP_TP") (pintype "input"))
      (node (ref "TP_3V3") (pin "TP") (pinfunction "TP_TP") (pintype "input"))
      (node (ref "U1") (pin "P$A22") (pinfunction "VDD_P$A22") (pintype "power_in"))
      (node (ref "U1") (pin "P$AD14") (pinfunction "VDD_P$AD14") (pintype "power_in"))
      (node (ref "U1") (pin "P$AD23") (pinfunction "VDD_P$AD23") (pintype "power_in"))
      (node (ref "U1") (pin "P$B1") (pinfunction "VDD_P$B1") (pintype "power_in"))
      (node (ref "U1") (pin "P$W1") (pinfunction "VDD_P$W1") (pintype "power_in"))
      (node (ref "U1") (pin "P$Y2") (pinfunction "VDDH_P$Y2") (pintype "power_in"))
    )
    (net (code "7") (name "ALERT") (class "Default")
      (node (ref "U1") (pin "P$J24") (pinfunction "P0.10/NFC2_P$J24") (pintype "bidirectional"))
      (node (ref "U3") (pin "5") (pinfunction "~{ALERT}_5") (pintype "output"))
    )
    (net (code "8") (name "D+") (class "Default")
      (node (ref "D3") (pin "4") (pinfunction "I/O2_2_4") (pintype "bidirectional"))
      (node (ref "U1") (pin "P$AD6") (pinfunction "D+_P$AD6") (pintype "bidirectional"))
    )
    (net (code "9") (name "D-") (class "Default")
      (node (ref "D3") (pin "6") (pinfunction "I/O1_2_6") (pintype "bidirectional"))
      (node (ref "U1") (pin "P$AD4") (pinfunction "D-_P$AD4") (pintype "bidirectional"))
    )
    (net (code "10") (name "DEC4_6") (class "Default")
      (node (ref "C10") (pin "1") (pinfunction "1_1") (pintype "passive"))
      (node (ref "C15") (pin "1") (pinfunction "1_1") (pintype "passive"))
      (node (ref "C16") (pin "1") (pinfunction "1_1") (pintype "passive"))
      (node (ref "L3") (pin "2") (pinfunction "2_2") (pintype "passive"))
      (node (ref "U1") (pin "P$B5") (pinfunction "DEC4_P$B5") (pintype "power_in"))
      (node (ref "U1") (pin "P$E24") (pinfunction "DEC6_P$E24") (pintype "bidirectional"))
    )
    (net (code "11") (name "DN") (class "Default")
      (node (ref "D3") (pin "1") (pinfunction "I/O1_1_1") (pintype "bidirectional"))
      (node (ref "J3") (pin "A7") (pinfunction "DN1_A7") (pintype "bidirectional"))
      (node (ref "J3") (pin "B7") (pinfunction "DN2_B7") (pintype "bidirectional"))
    )
    (net (code "12") (name "DP") (class "Default")
      (node (ref "D3") (pin "3") (pinfunction "I/O2_1_3") (pintype "bidirectional"))
      (node (ref "J3") (pin "A6") (pinfunction "DP1_A6") (pintype "bidirectional"))
      (node (ref "J3") (pin "B6") (pinfunction "DP2_B6") (pintype "bidirectional"))
    )
    (net (code "13") (name "EPD_3V3") (class "Default")
      (node (ref "C1-EP-DR") (pin "1") (pinfunction "1_1") (pintype "passive"))
      (node (ref "EPD_C5") (pin "2") (pinfunction "2_2") (pintype "passive"))
      (node (ref "J1") (pin "15") (pinfunction "15_15") (pintype "bidirectional"))
      (node (ref "J1") (pin "16") (pinfunction "16_16") (pintype "bidirectional"))
      (node (ref "L5") (pin "1") (pinfunction "1_1") (pintype "passive"))
      (node (ref "Q1") (pin "3") (pinfunction "D_3") (pintype "bidirectional"))
    )
    (net (code "14") (name "EPD_BUSY") (class "Default")
      (node (ref "J1") (pin "9") (pinfunction "9_9") (pintype "bidirectional"))
      (node (ref "U1") (pin "P$AD12") (pinfunction "P0.17_P$AD12") (pintype "bidirectional"))
    )
    (net (code "15") (name "EPD_CS") (class "Default")
      (node (ref "J1") (pin "12") (pinfunction "12_12") (pintype "bidirectional"))
      (node (ref "U1") (pin "P$K2") (pinfunction "P0.05/AIN3_P$K2") (pintype "bidirectional"))
    )
    (net (code "16") (name "EPD_DC") (class "Default")
      (node (ref "J1") (pin "11") (pinfunction "11_11") (pintype "bidirectional"))
      (node (ref "U1") (pin "P$AD10") (pinfunction "P0.15_P$AD10") (pintype "bidirectional"))
    )
    (net (code "17") (name "EPD_RST") (class "Default")
      (node (ref "J1") (pin "10") (pinfunction "10_10") (pintype "bidirectional"))
      (node (ref "U1") (pin "P$AC11") (pinfunction "P0.16_P$AC11") (pintype "bidirectional"))
    )
    (net (code "18") (name "GDR") (class "Default")
      (node (ref "J1") (pin "2") (pinfunction "2_2") (pintype "bidirectional"))
      (node (ref "Q3") (pin "1") (pinfunction "G_1") (pintype "bidirectional"))
      (node (ref "R2_EP_DR") (pin "2") (pinfunction "2_2") (pintype "bidirectional"))
    )
    (net (code "19") (name "GND") (class "Default")
      (node (ref "C1") (pin "2") (pinfunction "2_2") (pintype "passive"))
      (node (ref "C1-EP-DR") (pin "2") (pinfunction "2_2") (pintype "passive"))
      (node (ref "C10") (pin "2") (pinfunction "2_2") (pintype "passive"))
      (node (ref "C11") (pin "2") (pinfunction "2_2") (pintype "passive"))
      (node (ref "C12") (pin "2") (pinfunction "2_2") (pintype "passive"))
      (node (ref "C13") (pin "2") (pinfunction "2_2") (pintype "passive"))
      (node (ref "C14") (pin "2") (pinfunction "2_2") (pintype "passive"))
      (node (ref "C15") (pin "2") (pinfunction "2_2") (pintype "passive"))
      (node (ref "C16") (pin "2") (pinfunction "2_2") (pintype "passive"))
      (node (ref "C17") (pin "1") (pinfunction "1_1") (pintype "passive"))
      (node (ref "C18") (pin "1") (pinfunction "1_1") (pintype "passive"))
      (node (ref "C19") (pin "2") (pinfunction "2_2") (pintype "passive"))
      (node (ref "C2") (pin "2") (pinfunction "2_2") (pintype "passive"))
      (node (ref "C20") (pin "2") (pinfunction "2_2") (pintype "passive"))
      (node (ref "C21") (pin "2") (pinfunction "2_2") (pintype "passive"))
      (node (ref "C22") (pin "2") (pinfunction "2_2") (pintype "passive"))
      (node (ref "C23") (pin "1") (pinfunction "1_1") (pintype "passive"))
      (node (ref "C24") (pin "1") (pinfunction "1_1") (pintype "passive"))
      (node (ref "C25") (pin "2") (pinfunction "2_2") (pintype "passive"))
      (node (ref "C27") (pin "2") (pinfunction "2_2") (pintype "passive"))
      (node (ref "C29") (pin "2") (pinfunction "2_2") (pintype "passive"))
      (node (ref "C3") (pin "2") (pinfunction "2_2") (pintype "passive"))
      (node (ref "C30") (pin "2") (pinfunction "2_2") (pintype "passive"))
      (node (ref "C31") (pin "2") (pinfunction "2_2") (pintype "passive"))
      (node (ref "C32") (pin "2") (pinfunction "2_2") (pintype "passive"))
      (node (ref "C33") (pin "2") (pinfunction "2_2") (pintype "passive"))
      (node (ref "C34") (pin "2") (pinfunction "2_2") (pintype "passive"))
      (node (ref "C37") (pin "1") (pinfunction "1_1") (pintype "passive"))
      (node (ref "C38") (pin "2") (pinfunction "2_2") (pintype "passive"))
      (node (ref "C39") (pin "2") (pinfunction "2_2") (pintype "passive"))
      (node (ref "C4") (pin "2") (pinfunction "2_2") (pintype "passive"))
      (node (ref "C42") (pin "2") (pinfunction "2_2") (pintype "passive"))
      (node (ref "C43") (pin "2") (pinfunction "2_2") (pintype "passive"))
      (node (ref "C5") (pin "2") (pinfunction "2_2") (pintype "passive"))
      (node (ref "C6") (pin "2") (pinfunction "2_2") (pintype "passive"))
      (node (ref "C7") (pin "2") (pinfunction "2_2") (pintype "passive"))
      (node (ref "C8") (pin "2") (pinfunction "2_2") (pintype "passive"))
      (node (ref "C9") (pin "2") (pinfunction "2_2") (pintype "passive"))
      (node (ref "D3") (pin "2") (pinfunction "GND_2") (pintype "bidirectional"))
      (node (ref "D4") (pin "1") (pinfunction "K_1") (pintype "bidirectional"))
      (node (ref "EPD_C1") (pin "1") (pinfunction "1_1") (pintype "passive"))
      (node (ref "EPD_C10") (pin "1") (pinfunction "1_1") (pintype "passive"))
      (node (ref "EPD_C11") (pin "1") (pinfunction "1_1") (pintype "passive"))
      (node (ref "EPD_C12") (pin "1") (pinfunction "1_1") (pintype "passive"))
      (node (ref "EPD_C2") (pin "1") (pinfunction "1_1") (pintype "passive"))
      (node (ref "EPD_C5") (pin "1") (pinfunction "1_1") (pintype "passive"))
      (node (ref "EPD_C6") (pin "1") (pinfunction "1_1") (pintype "passive"))
      (node (ref "EPD_C7") (pin "1") (pinfunction "1_1") (pintype "passive"))
      (node (ref "EPD_C8") (pin "1") (pinfunction "1_1") (pintype "passive"))
      (node (ref "EPD_C9") (pin "1") (pinfunction "1_1") (pintype "passive"))
      (node (ref "IC1") (pin "D2") (pinfunction "GND_D2") (pintype "bidirectional"))
      (node (ref "IC2") (pin "B1") (pinfunction "IN/TRIG_B1") (pintype "bidirectional"))
      (node (ref "IC2") (pin "B3") (pinfunction "GND_B3") (pintype "bidirectional"))
      (node (ref "IC3") (pin "8") (pinfunction "GNDIO_8") (pintype "bidirectional"))
      (node (ref "IC3") (pin "9") (pinfunction "GND_9") (pintype "bidirectional"))
      (node (ref "IC9") (pin "B1") (pinfunction "VSEL_B1") (pintype "bidirectional"))
      (node (ref "IC9") (pin "C1") (pinfunction "AGND_C1") (pintype "bidirectional"))
      (node (ref "IC9") (pin "C2") (pinfunction "PGND_1_C2") (pintype "bidirectional"))
      (node (ref "IC9") (pin "C3") (pinfunction "PGND_2_C3") (pintype "bidirectional"))
      (node (ref "J1") (pin "17") (pinfunction "17_17") (pintype "bidirectional"))
      (node (ref "J1") (pin "8") (pinfunction "8_8") (pintype "bidirectional"))
      (node (ref "J1") (pin "MP1") (pinfunction "MP1_MP1") (pintype "bidirectional"))
      (node (ref "J1") (pin "MP2") (pinfunction "MP2_MP2") (pintype "bidirectional"))
      (node (ref "J2") (pin "3") (pinfunction "3_3") (pintype "bidirectional"))
      (node (ref "J2") (pin "5") (pinfunction "5_5") (pintype "bidirectional"))
      (node (ref "J3") (pin "A12_B1") (pinfunction "GND_A12_B1") (pintype "power_in"))
      (node (ref "J3") (pin "A1_B12") (pinfunction "GND_A1_B12") (pintype "power_in"))
      (node (ref "J3") (pin "SH1") (pinfunction "SHIELD_SH1") (pintype "passive"))
      (node (ref "J3") (pin "SH2") (pinfunction "SHIELD_SH2") (pintype "passive"))
      (node (ref "J3") (pin "SH3") (pinfunction "SHIELD_SH3") (pintype "passive"))
      (node (ref "J3") (pin "SH4") (pinfunction "SHIELD_SH4") (pintype "passive"))
      (node (ref "R1_USB") (pin "1") (pinfunction "1_1") (pintype "bidirectional"))
      (node (ref "R2_EP_DR") (pin "1") (pinfunction "1_1") (pintype "bidirectional"))
      (node (ref "R2_USB") (pin "2") (pinfunction "2_2") (pintype "bidirectional"))
      (node (ref "R3") (pin "1") (pinfunction "1_1") (pintype "bidirectional"))
      (node (ref "R9") (pin "1") (pinfunction "1_1") (pintype "bidirectional"))
      (node (ref "R_TYPE_SEL") (pin "1") (pinfunction "1_1") (pintype "bidirectional"))
      (node (ref "SJ1") (pin "1") (pinfunction "1_1") (pintype "passive"))
      (node (ref "SW_DN") (pin "1") (pinfunction "1_1") (pintype "passive"))
      (node (ref "SW_ENT") (pin "1") (pinfunction "1_1") (pintype "passive"))
      (node (ref "SW_UP") (pin "1") (pinfunction "1_1") (pintype "passive"))
      (node (ref "TP_BAT_GND") (pin "TP") (pinfunction "TP_TP") (pintype "input"))
      (node (ref "TP_GND") (pin "TP") (pinfunction "TP_TP") (pintype "input"))
      (node (ref "U1") (pin "P$74") (pinfunction "VSS_PAD_P$74") (pintype "bidirectional"))
      (node (ref "U1") (pin "P$75") (pinfunction "VSS_PAD_P$75") (pintype "bidirectional"))
      (node (ref "U1") (pin "P$76") (pinfunction "VSS_PAD_P$76") (pintype "bidirectional"))
      (node (ref "U1") (pin "P$77") (pinfunction "VSS_PAD_P$77") (pintype "bidirectional"))
      (node (ref "U1") (pin "P$78") (pinfunction "VSS_PAD_P$78") (pintype "bidirectional"))
      (node (ref "U1") (pin "P$79") (pinfunction "VSS_PAD_P$79") (pintype "bidirectional"))
      (node (ref "U1") (pin "P$80") (pinfunction "VSS_PAD_P$80") (pintype "bidirectional"))
      (node (ref "U1") (pin "P$81") (pinfunction "VSS_PAD_P$81") (pintype "bidirectional"))
      (node (ref "U1") (pin "P$82") (pinfunction "VSS_PAD_P$82") (pintype "bidirectional"))
      (node (ref "U1") (pin "P$83") (pinfunction "VSS_PAD_P$83") (pintype "bidirectional"))
      (node (ref "U1") (pin "P$84") (pinfunction "VSS_PAD_P$84") (pintype "bidirectional"))
      (node (ref "U1") (pin "P$85") (pinfunction "VSS_PAD_P$85") (pintype "bidirectional"))
      (node (ref "U1") (pin "P$86") (pinfunction "VSS_PAD_P$86") (pintype "bidirectional"))
      (node (ref "U1") (pin "P$87") (pinfunction "VSS_PAD_P$87") (pintype "bidirectional"))
      (node (ref "U1") (pin "P$88") (pinfunction "VSS_PAD_P$88") (pintype "bidirectional"))
      (node (ref "U1") (pin "P$89") (pinfunction "VSS_PAD_P$89") (pintype "bidirectional"))
      (node (ref "U1") (pin "P$90") (pinfunction "VSS_PAD_P$90") (pintype "bidirectional"))
      (node (ref "U1") (pin "P$B7") (pinfunction "VSS_P$B7") (pintype "power_in"))
      (node (ref "U1") (pin "P$F23") (pinfunction "VSS_PA_P$F23") (pintype "bidirectional"))
      (node (ref "U3") (pin "1") (pinfunction "CTG_1") (pintype "power_in"))
      (node (ref "U3") (pin "4") (pinfunction "GND_4") (pintype "power_in"))
      (node (ref "U3") (pin "6") (pinfunction "QSTRT_6") (pintype "input"))
      (node (ref "U3") (pin "9") (pinfunction "EP_9") (pintype "power_in"))
      (node (ref "X1") (pin "2") (pinfunction "2_2") (pintype "passive"))
      (node (ref "X1") (pin "4") (pinfunction "4_4") (pintype "passive"))
    )
    (net (code "20") (name "HAPTIC_EN") (class "Default")
      (node (ref "IC2") (pin "A1") (pinfunction "EN_A1") (pintype "bidirectional"))
      (node (ref "U1") (pin "P$U1") (pinfunction "P0.12_P$U1") (pintype "bidirectional"))
    )
    (net (code "21") (name "IMU_INT1") (class "Default")
      (node (ref "IC3") (pin "5") (pinfunction "INT1_5") (pintype "bidirectional"))
      (node (ref "U1") (pin "P$N1") (pinfunction "P0.08_P$N1") (pintype "bidirectional"))
    )
    (net (code "22") (name "IMU_INT2") (class "Default")
      (node (ref "IC3") (pin "6") (pinfunction "INT2_6") (pintype "bidirectional"))
      (node (ref "U1") (pin "P$P2") (pinfunction "P1.08_P$P2") (pintype "bidirectional"))
    )
    (net (code "23") (name "LX1") (class "Default")
      (node (ref "IC9") (pin "B2") (pinfunction "SW1_1_B2") (pintype "bidirectional"))
      (node (ref "IC9") (pin "B3") (pinfunction "SW1_2_B3") (pintype "bidirectional"))
      (node (ref "L7") (pin "1") (pinfunction "1_1") (pintype "bidirectional"))
    )
    (net (code "24") (name "LX2") (class "Default")
      (node (ref "IC9") (pin "D2") (pinfunction "SW2_1_D2") (pintype "bidirectional"))
      (node (ref "IC9") (pin "D3") (pinfunction "SW2_2_D3") (pintype "bidirectional"))
      (node (ref "L7") (pin "2") (pinfunction "2_2") (pintype "bidirectional"))
    )
    (net (code "25") (name "MOSI") (class "Default")
      (node (ref "J1") (pin "14") (pinfunction "14_14") (pintype "bidirectional"))
      (node (ref "U1") (pin "P$B13") (pinfunction "P0.03/AIN1_P$B13") (pintype "bidirectional"))
    )
    (net (code "26") (name "Net-(D2-K)") (class "Default")
      (node (ref "C2-EP-DR") (pin "1") (pinfunction "1_1") (pintype "passive"))
      (node (ref "D2") (pin "1") (pinfunction "K_1") (pintype "bidirectional"))
      (node (ref "D4") (pin "2") (pinfunction "A_2") (pintype "bidirectional"))
    )
    (net (code "27") (name "Net-(D5-A)") (class "Default")
      (node (ref "C2-EP-DR") (pin "2") (pinfunction "2_2") (pintype "passive"))
      (node (ref "D5") (pin "2") (pinfunction "A_2") (pintype "bidirectional"))
      (node (ref "L5") (pin "2") (pinfunction "2_2") (pintype "passive"))
      (node (ref "Q3") (pin "3") (pinfunction "D_3") (pintype "bidirectional"))
    )
    (net (code "28") (name "Net-(EPD_C1-Pad2)") (class "Default")
      (node (ref "EPD_C1") (pin "2") (pinfunction "2_2") (pintype "passive"))
      (node (ref "J1") (pin "5") (pinfunction "5_5") (pintype "bidirectional"))
    )
    (net (code "29") (name "Net-(EPD_C2-Pad2)") (class "Default")
      (node (ref "EPD_C2") (pin "2") (pinfunction "2_2") (pintype "passive"))
      (node (ref "J1") (pin "4") (pinfunction "4_4") (pintype "bidirectional"))
    )
    (net (code "30") (name "Net-(EPD_C6-Pad2)") (class "Default")
      (node (ref "EPD_C6") (pin "2") (pinfunction "2_2") (pintype "passive"))
      (node (ref "J1") (pin "18") (pinfunction "18_18") (pintype "bidirectional"))
    )
    (net (code "31") (name "Net-(EPD_C7-Pad2)") (class "Default")
      (node (ref "EPD_C7") (pin "2") (pinfunction "2_2") (pintype "passive"))
      (node (ref "J1") (pin "19") (pinfunction "19_19") (pintype "bidirectional"))
    )
    (net (code "32") (name "Net-(EPD_C8-Pad2)") (class "Default")
      (node (ref "EPD_C8") (pin "2") (pinfunction "2_2") (pintype "passive"))
      (node (ref "J1") (pin "20") (pinfunction "20_20") (pintype "bidirectional"))
    )
    (net (code "33") (name "Net-(EPD_C10-Pad2)") (class "Default")
      (node (ref "EPD_C10") (pin "2") (pinfunction "2_2") (pintype "passive"))
      (node (ref "J1") (pin "22") (pinfunction "22_22") (pintype "bidirectional"))
    )
    (net (code "34") (name "Net-(EPD_C12-Pad2)") (class "Default")
      (node (ref "EPD_C12") (pin "2") (pinfunction "2_2") (pintype "passive"))
      (node (ref "J1") (pin "24") (pinfunction "24_24") (pintype "bidirectional"))
    )
    (net (code "35") (name "Net-(IC1-TS{slash}MR)") (class "Default")
      (node (ref "IC1") (pin "D1") (pinfunction "TS/MR_D1") (pintype "bidirectional"))
      (node (ref "R9") (pin "2") (pinfunction "2_2") (pintype "bidirectional"))
    )
    (net (code "36") (name "Net-(IC2-REG)") (class "Default")
      (node (ref "C32") (pin "1") (pinfunction "1_1") (pintype "passive"))
      (node (ref "IC2") (pin "A2") (pinfunction "REG_A2") (pintype "bidirectional"))
    )
    (net (code "37") (name "Net-(IC3-SDO)") (class "Default")
      (node (ref "IC3") (pin "1") (pinfunction "SDO_1") (pintype "bidirectional"))
      (node (ref "R3") (pin "2") (pinfunction "2_2") (pintype "bidirectional"))
    )
    (net (code "38") (name "Net-(IC9-SCL)") (class "Default")
      (node (ref "IC9") (pin "D1") (pinfunction "SCL_D1") (pintype "bidirectional"))
      (node (ref "R4") (pin "2") (pinfunction "2_2") (pintype "bidirectional"))
    )
    (net (code "39") (name "Net-(IC9-SDA)") (class "Default")
      (node (ref "IC9") (pin "E1") (pinfunction "SDA_E1") (pintype "bidirectional"))
      (node (ref "R2") (pin "2") (pinfunction "2_2") (pintype "bidirectional"))
    )
    (net (code "40") (name "Net-(J3-CC1)") (class "Default")
      (node (ref "J3") (pin "A5") (pinfunction "CC1_A5") (pintype "bidirectional"))
      (node (ref "R1_USB") (pin "2") (pinfunction "2_2") (pintype "bidirectional"))
    )
    (net (code "41") (name "Net-(J3-CC2)") (class "Default")
      (node (ref "J3") (pin "B5") (pinfunction "CC2_B5") (pintype "bidirectional"))
      (node (ref "R2_USB") (pin "1") (pinfunction "1_1") (pintype "bidirectional"))
    )
    (net (code "42") (name "Net-(L2-Pad2)") (class "Default")
      (node (ref "L2") (pin "2") (pinfunction "2_2") (pintype "passive"))
      (node (ref "L3") (pin "1") (pinfunction "1_1") (pintype "passive"))
    )
    (net (code "43") (name "Net-(R1_EP_DR-Pad1)") (class "Default")
      (node (ref "R1_EP_DR") (pin "1") (pinfunction "1_1") (pintype "bidirectional"))
      (node (ref "R_TYPE_SEL") (pin "2") (pinfunction "2_2") (pintype "bidirectional"))
      (node (ref "SJ1") (pin "2") (pinfunction "2_2") (pintype "passive"))
    )
    (net (code "44") (name "Net-(U1-ANT)") (class "Default")
      (node (ref "C3") (pin "1") (pinfunction "1_1") (pintype "passive"))
      (node (ref "L1") (pin "1") (pinfunction "1_1") (pintype "passive"))
      (node (ref "U1") (pin "P$H23") (pinfunction "ANT_P$H23") (pintype "bidirectional"))
    )
    (net (code "45") (name "Net-(U1-DCC)") (class "Default")
      (node (ref "L2") (pin "1") (pinfunction "1_1") (pintype "passive"))
      (node (ref "U1") (pin "P$B3") (pinfunction "DCC_P$B3") (pintype "output"))
    )
    (net (code "46") (name "Net-(U1-DEC2)") (class "Default")
      (node (ref "C13") (pin "1") (pinfunction "1_1") (pintype "passive"))
      (node (ref "U1") (pin "P$A18") (pinfunction "DEC2_P$A18") (pintype "bidirectional"))
    )
    (net (code "47") (name "Net-(U1-DEC3V3)") (class "Default")
      (node (ref "C20") (pin "1") (pinfunction "1_1") (pintype "passive"))
      (node (ref "U1") (pin "P$AC5") (pinfunction "DEC3V3_P$AC5") (pintype "bidirectional"))
    )
    (net (code "48") (name "Net-(U1-DEC5)") (class "Default")
      (node (ref "C9") (pin "1") (pinfunction "1_1") (pintype "passive"))
      (node (ref "U1") (pin "P$N24") (pinfunction "DEC5_P$N24") (pintype "bidirectional"))
    )
    (net (code "49") (name "Net-(U1-XC1)") (class "Default")
      (node (ref "C1") (pin "1") (pinfunction "1_1") (pintype "passive"))
      (node (ref "U1") (pin "P$B24") (pinfunction "XC1_P$B24") (pintype "input"))
      (node (ref "X1") (pin "1") (pinfunction "1_1") (pintype "passive"))
    )
    (net (code "50") (name "Net-(U1-XC2)") (class "Default")
      (node (ref "C2") (pin "1") (pinfunction "1_1") (pintype "passive"))
      (node (ref "U1") (pin "P$A23") (pinfunction "XC2_P$A23") (pintype "output"))
      (node (ref "X1") (pin "3") (pinfunction "3_3") (pintype "passive"))
    )
    (net (code "51") (name "OUT+") (class "Default")
      (node (ref "IC2") (pin "A3") (pinfunction "OUT+_A3") (pintype "bidirectional"))
      (node (ref "TP_OP") (pin "TP") (pinfunction "TP_TP") (pintype "input"))
    )
    (net (code "52") (name "OUT-") (class "Default")
      (node (ref "IC2") (pin "C3") (pinfunction "OUT-_C3") (pintype "bidirectional"))
      (node (ref "TP_ON") (pin "TP") (pinfunction "TP_TP") (pintype "input"))
    )
    (net (code "53") (name "P0.04") (class "Default")
      (node (ref "U1") (pin "P$J1") (pinfunction "P0.04/AIN2_P$J1") (pintype "bidirectional"))
    )
    (net (code "54") (name "P0.09") (class "Default")
      (node (ref "U1") (pin "P$L24") (pinfunction "P0.09/NFC1_P$L24") (pintype "bidirectional"))
    )
    (net (code "55") (name "P0.13") (class "Default")
      (node (ref "C30") (pin "1") (pinfunction "1_1") (pintype "passive"))
      (node (ref "R5") (pin "1") (pinfunction "1_1") (pintype "bidirectional"))
      (node (ref "SW_UP") (pin "2") (pinfunction "2_2") (pintype "passive"))
      (node (ref "U1") (pin "P$AD8") (pinfunction "P0.13_P$AD8") (pintype "bidirectional"))
    )
    (net (code "56") (name "P0.14") (class "Default")
      (node (ref "C31") (pin "1") (pinfunction "1_1") (pintype "passive"))
      (node (ref "R8") (pin "1") (pinfunction "1_1") (pintype "bidirectional"))
      (node (ref "SW_ENT") (pin "2") (pinfunction "2_2") (pintype "passive"))
      (node (ref "U1") (pin "P$AC9") (pinfunction "P0.14_P$AC9") (pintype "bidirectional"))
    )
    (net (code "57") (name "P0.19") (class "Default")
      (node (ref "U1") (pin "P$AC15") (pinfunction "P0.19_P$AC15") (pintype "bidirectional"))
    )
    (net (code "58") (name "P0.20") (class "Default")
      (node (ref "U1") (pin "P$AD16") (pinfunction "P0.20_P$AD16") (pintype "bidirectional"))
    )
    (net (code "59") (name "P0.21") (class "Default")
      (node (ref "U1") (pin "P$AC17") (pinfunction "P0.21_P$AC17") (pintype "bidirectional"))
    )
    (net (code "60") (name "P0.22") (class "Default")
      (node (ref "U1") (pin "P$AD18") (pinfunction "P0.22_P$AD18") (pintype "bidirectional"))
    )
    (net (code "61") (name "P0.23") (class "Default")
      (node (ref "U1") (pin "P$AC19") (pinfunction "P0.23_P$AC19") (pintype "bidirectional"))
    )
    (net (code "62") (name "P0.24") (class "Default")
      (node (ref "U1") (pin "P$AD20") (pinfunction "P0.24_P$AD20") (pintype "bidirectional"))
    )
    (net (code "63") (name "P0.25") (class "Default")
      (node (ref "U1") (pin "P$AC21") (pinfunction "P0.25_P$AC21") (pintype "bidirectional"))
    )
    (net (code "64") (name "P0.26") (class "Default")
      (node (ref "U1") (pin "P$G1") (pinfunction "P0.26_P$G1") (pintype "bidirectional"))
    )
    (net (code "65") (name "P0.27") (class "Default")
      (node (ref "U1") (pin "P$H2") (pinfunction "P0.27_P$H2") (pintype "bidirectional"))
    )
    (net (code "66") (name "P0.28") (class "Default")
      (node (ref "U1") (pin "P$B11") (pinfunction "P0.28/AIN4_P$B11") (pintype "bidirectional"))
    )
    (net (code "67") (name "P0.29") (class "Default")
      (node (ref "U1") (pin "P$A10") (pinfunction "P0.29/AIN5_P$A10") (pintype "bidirectional"))
    )
    (net (code "68") (name "P0.30") (class "Default")
      (node (ref "U1") (pin "P$B9") (pinfunction "P0.30/AIN6_P$B9") (pintype "bidirectional"))
    )
    (net (code "69") (name "P0.31") (class "Default")
      (node (ref "U1") (pin "P$A8") (pinfunction "P0.31/AIN7_P$A8") (pintype "bidirectional"))
    )
    (net (code "70") (name "P1.01") (class "Default")
      (node (ref "Q1") (pin "1") (pinfunction "G_1") (pintype "bidirectional"))
      (node (ref "R_PWR_EPD") (pin "1") (pinfunction "1_1") (pintype "bidirectional"))
      (node (ref "U1") (pin "P$Y23") (pinfunction "P1.01_P$Y23") (pintype "bidirectional"))
    )
    (net (code "71") (name "P1.02") (class "Default")
      (node (ref "C29") (pin "1") (pinfunction "1_1") (pintype "passive"))
      (node (ref "R7") (pin "1") (pinfunction "1_1") (pintype "bidirectional"))
      (node (ref "SW_DN") (pin "2") (pinfunction "2_2") (pintype "passive"))
      (node (ref "U1") (pin "P$W24") (pinfunction "P1.02_P$W24") (pintype "bidirectional"))
    )
    (net (code "72") (name "P1.03") (class "Default")
      (node (ref "U1") (pin "P$V23") (pinfunction "P1.03_P$V23") (pintype "bidirectional"))
    )
    (net (code "73") (name "P1.04") (class "Default")
      (node (ref "U1") (pin "P$U24") (pinfunction "P1.04_P$U24") (pintype "bidirectional"))
    )
    (net (code "74") (name "P1.05") (class "Default")
      (node (ref "U1") (pin "P$T23") (pinfunction "P1.05_P$T23") (pintype "bidirectional"))
    )
    (net (code "75") (name "P1.06") (class "Default")
      (node (ref "U1") (pin "P$R24") (pinfunction "P1.06_P$R24") (pintype "bidirectional"))
    )
    (net (code "76") (name "P1.07") (class "Default")
      (node (ref "U1") (pin "P$P23") (pinfunction "P1.07_P$P23") (pintype "bidirectional"))
    )
    (net (code "77") (name "P1.09") (class "Default")
      (node (ref "U1") (pin "P$R1") (pinfunction "P1.09_P$R1") (pintype "bidirectional"))
    )
    (net (code "78") (name "P1.10") (class "Default")
      (node (ref "U1") (pin "P$A20") (pinfunction "P1.10_P$A20") (pintype "bidirectional"))
    )
    (net (code "79") (name "P1.11") (class "Default")
      (node (ref "U1") (pin "P$B19") (pinfunction "P1.11_P$B19") (pintype "bidirectional"))
    )
    (net (code "80") (name "P1.12") (class "Default")
      (node (ref "U1") (pin "P$B17") (pinfunction "P1.12_P$B17") (pintype "bidirectional"))
    )
    (net (code "81") (name "P1.13") (class "Default")
      (node (ref "U1") (pin "P$A16") (pinfunction "P1.13_P$A16") (pintype "bidirectional"))
    )
    (net (code "82") (name "P1.14") (class "Default")
      (node (ref "U1") (pin "P$B15") (pinfunction "P1.14_P$B15") (pintype "bidirectional"))
    )
    (net (code "83") (name "P1.15") (class "Default")
      (node (ref "U1") (pin "P$A14") (pinfunction "P1.15_P$A14") (pintype "bidirectional"))
    )
    (net (code "84") (name "PMIC_INT") (class "Default")
      (node (ref "IC1") (pin "A1") (pinfunction "~{INT}_A1") (pintype "bidirectional"))
      (node (ref "U1") (pin "P$T2") (pinfunction "P0.11_P$T2") (pintype "bidirectional"))
    )
    (net (code "85") (name "PREVGH") (class "Default")
      (node (ref "D5") (pin "1") (pinfunction "K_1") (pintype "bidirectional"))
      (node (ref "EPD_C9") (pin "2") (pinfunction "2_2") (pintype "passive"))
      (node (ref "J1") (pin "21") (pinfunction "21_21") (pintype "bidirectional"))
    )
    (net (code "86") (name "PREVGL") (class "Default")
      (node (ref "D2") (pin "2") (pinfunction "A_2") (pintype "bidirectional"))
      (node (ref "EPD_C11") (pin "2") (pinfunction "2_2") (pintype "passive"))
      (node (ref "J1") (pin "23") (pinfunction "23_23") (pintype "bidirectional"))
    )
    (net (code "87") (name "RESE") (class "Default")
      (node (ref "Q3") (pin "2") (pinfunction "S_2") (pintype "bidirectional"))
      (node (ref "R1_EP_DR") (pin "2") (pinfunction "2_2") (pintype "bidirectional"))
    )
    (net (code "88") (name "RESET") (class "Default")
      (node (ref "J1") (pin "3") (pinfunction "3_3") (pintype "bidirectional"))
      (node (ref "J2") (pin "6") (pinfunction "6_6") (pintype "bidirectional"))
      (node (ref "TP_RESET") (pin "TP") (pinfunction "TP_TP") (pintype "input"))
      (node (ref "U1") (pin "P$AC13") (pinfunction "P0.18/RESET_P$AC13") (pintype "bidirectional"))
    )
    (net (code "89") (name "SCK") (class "Default")
      (node (ref "J1") (pin "13") (pinfunction "13_13") (pintype "bidirectional"))
      (node (ref "U1") (pin "P$A12") (pinfunction "P0.02/AIN0_P$A12") (pintype "bidirectional"))
    )
    (net (code "90") (name "SCL") (class "Default")
      (node (ref "IC1") (pin "B1") (pinfunction "SCL_B1") (pintype "bidirectional"))
      (node (ref "IC2") (pin "C1") (pinfunction "SCL_C1") (pintype "bidirectional"))
      (node (ref "IC3") (pin "12") (pinfunction "SCX_12") (pintype "bidirectional"))
      (node (ref "R17") (pin "2") (pinfunction "2_2") (pintype "bidirectional"))
      (node (ref "R4") (pin "1") (pinfunction "1_1") (pintype "bidirectional"))
      (node (ref "TP_SCL") (pin "TP") (pinfunction "TP_TP") (pintype "input"))
      (node (ref "U1") (pin "P$M2") (pinfunction "P0.07_P$M2") (pintype "bidirectional"))
      (node (ref "U3") (pin "7") (pinfunction "SCL_7") (pintype "input"))
    )
    (net (code "91") (name "SDA") (class "Default")
      (node (ref "IC1") (pin "C1") (pinfunction "SDA_C1") (pintype "bidirectional"))
      (node (ref "IC2") (pin "B2") (pinfunction "SDA_B2") (pintype "bidirectional"))
      (node (ref "IC3") (pin "2") (pinfunction "SDX_2") (pintype "bidirectional"))
      (node (ref "R18") (pin "2") (pinfunction "2_2") (pintype "bidirectional"))
      (node (ref "R2") (pin "1") (pinfunction "1_1") (pintype "bidirectional"))
      (node (ref "TP_SDA") (pin "TP") (pinfunction "TP_TP") (pintype "input"))
      (node (ref "U1") (pin "P$L1") (pinfunction "P0.06_P$L1") (pintype "bidirectional"))
      (node (ref "U3") (pin "8") (pinfunction "SDA_8") (pintype "bidirectional"))
    )
    (net (code "92") (name "SWDCLK") (class "Default")
      (node (ref "J2") (pin "4") (pinfunction "4_4") (pintype "bidirectional"))
      (node (ref "TP_SWDCLK") (pin "TP") (pinfunction "TP_TP") (pintype "input"))
      (node (ref "U1") (pin "P$AA24") (pinfunction "SWDCLK_P$AA24") (pintype "input"))
    )
    (net (code "93") (name "SWDIO") (class "Default")
      (node (ref "J2") (pin "2") (pinfunction "2_2") (pintype "bidirectional"))
      (node (ref "TP_SWDIO") (pin "TP") (pinfunction "TP_TP") (pintype "input"))
      (node (ref "U1") (pin "P$AC24") (pinfunction "SWDIO_P$AC24") (pintype "bidirectional"))
    )
    (net (code "94") (name "SWO") (class "Default")
      (node (ref "TP_SWO") (pin "TP") (pinfunction "TP_TP") (pintype "input"))
      (node (ref "U1") (pin "P$AD22") (pinfunction "P1.00_P$AD22") (pintype "bidirectional"))
    )
    (net (code "95") (name "VBAT") (class "Default")
      (node (ref "C27") (pin "1") (pinfunction "1_1") (pintype "passive"))
      (node (ref "C37") (pin "2") (pinfunction "2_2") (pintype "passive"))
      (node (ref "IC1") (pin "C2") (pinfunction "BAT_C2") (pintype "bidirectional"))
      (node (ref "TP_VBAT") (pin "TP") (pinfunction "TP_TP") (pintype "input"))
      (node (ref "U3") (pin "2") (pinfunction "CELL_2") (pintype "power_in"))
      (node (ref "U3") (pin "3") (pinfunction "VDD_3") (pintype "power_in"))
    )
    (net (code "96") (name "VBUS") (class "Default")
      (node (ref "C21") (pin "1") (pinfunction "1_1") (pintype "passive"))
      (node (ref "C38") (pin "1") (pinfunction "1_1") (pintype "passive"))
      (node (ref "C42") (pin "1") (pinfunction "1_1") (pintype "passive"))
      (node (ref "C43") (pin "1") (pinfunction "1_1") (pintype "passive"))
      (node (ref "D3") (pin "5") (pinfunction "VBUS_5") (pintype "bidirectional"))
      (node (ref "IC1") (pin "A2") (pinfunction "IN_A2") (pintype "bidirectional"))
      (node (ref "J3") (pin "A4_B9") (pinfunction "VBUS_A4_B9") (pintype "power_in"))
      (node (ref "J3") (pin "A9_B4") (pinfunction "VBUS_A9_B4") (pintype "power_in"))
      (node (ref "U1") (pin "P$AD2") (pinfunction "VBUS_P$AD2") (pintype "power_in"))
    )
    (net (code "97") (name "VREG") (class "Default")
      (node (ref "C23") (pin "2") (pinfunction "2_2") (pintype "passive"))
      (node (ref "C24") (pin "2") (pinfunction "2_2") (pintype "passive"))
      (node (ref "C39") (pin "1") (pinfunction "1_1") (pintype "passive"))
      (node (ref "IC1") (pin "B2") (pinfunction "SYS_B2") (pintype "bidirectional"))
      (node (ref "IC9") (pin "A1") (pinfunction "EN_A1") (pintype "bidirectional"))
      (node (ref "IC9") (pin "A2") (pinfunction "VIN_1_A2") (pintype "bidirectional"))
      (node (ref "IC9") (pin "A3") (pinfunction "VIN_2_A3") (pintype "bidirectional"))
      (node (ref "TP_VREG") (pin "TP") (pinfunction "TP_TP") (pintype "input"))
    )
    (net (code "98") (name "unconnected-(ANT1-NC-Pad2)") (class "Default")
      (node (ref "ANT1") (pin "2") (pinfunction "NC_2") (pintype "no_connect"))
    )
    (net (code "99") (name "unconnected-(IC3-ASCL-Pad11)") (class "Default")
      (node (ref "IC3") (pin "11") (pinfunction "ASCL_11") (pintype "bidirectional"))
    )
    (net (code "100") (name "unconnected-(IC3-ASDA-Pad4)") (class "Default")
      (node (ref "IC3") (pin "4") (pinfunction "ASDA_4") (pintype "bidirectional"))
    )
    (net (code "101") (name "unconnected-(J1-Pad1)") (class "Default")
      (node (ref "J1") (pin "1") (pinfunction "1_1") (pintype "bidirectional"))
    )
    (net (code "102") (name "unconnected-(J1-Pad6)") (class "Default")
      (node (ref "J1") (pin "6") (pinfunction "6_6") (pintype "bidirectional"))
    )
    (net (code "103") (name "unconnected-(J1-Pad7)") (class "Default")
      (node (ref "J1") (pin "7") (pinfunction "7_7") (pintype "bidirectional"))
    )
    (net (code "104") (name "unconnected-(J3-SBU1-PadA8)") (class "Default")
      (node (ref "J3") (pin "A8") (pinfunction "SBU1_A8") (pintype "bidirectional"))
    )
    (net (code "105") (name "unconnected-(J3-SBU2-PadB8)") (class "Default")
      (node (ref "J3") (pin "B8") (pinfunction "SBU2_B8") (pintype "bidirectional"))
    )
    (net (code "106") (name "unconnected-(U1-DCCH-PadP$AB2)") (class "Default")
      (node (ref "U1") (pin "P$AB2") (pinfunction "DCCH_P$AB2") (pintype "bidirectional"))
    )
  )
)
